# TU_ADV_SCH.net
KiCad netlist of a schematic drawn in Altium Designer
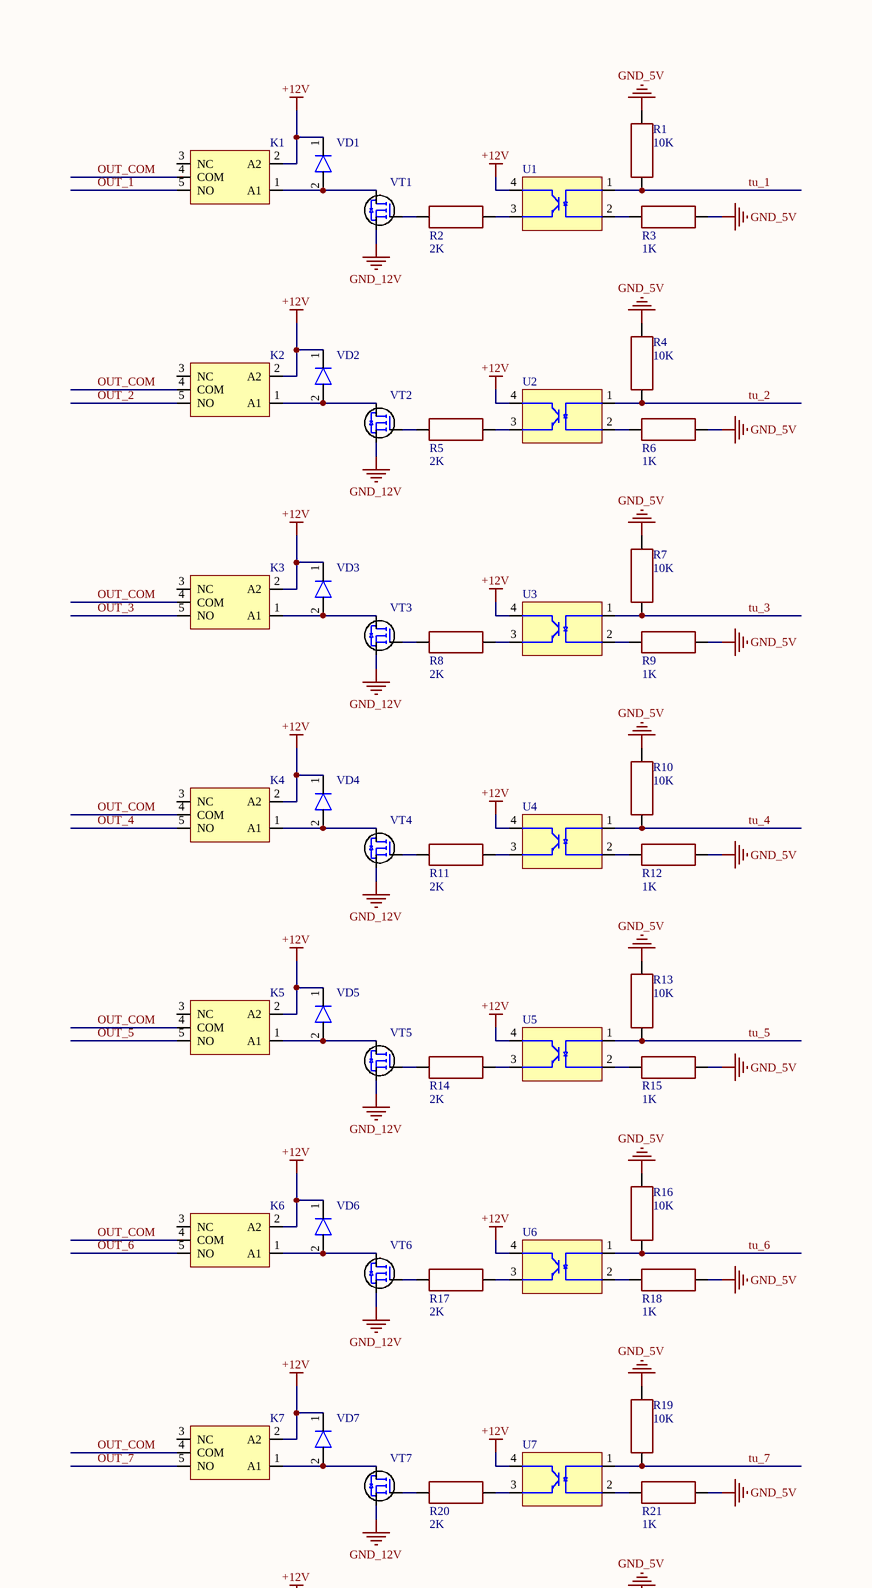
[diagram p0: TU_ADV_SCH.SchDoc, row 1 of 5 left]
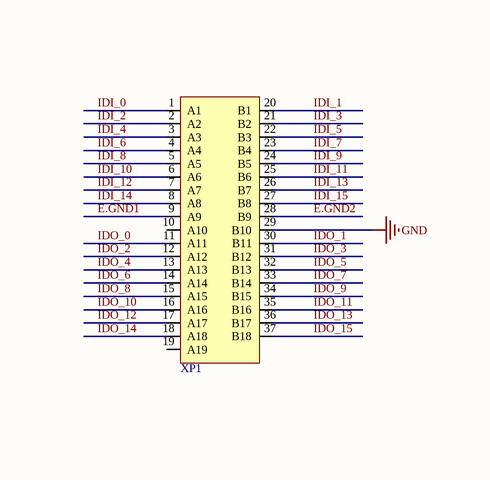
[diagram p1: TU_ADV_SCH.SchDoc, row 1 of 5 right]
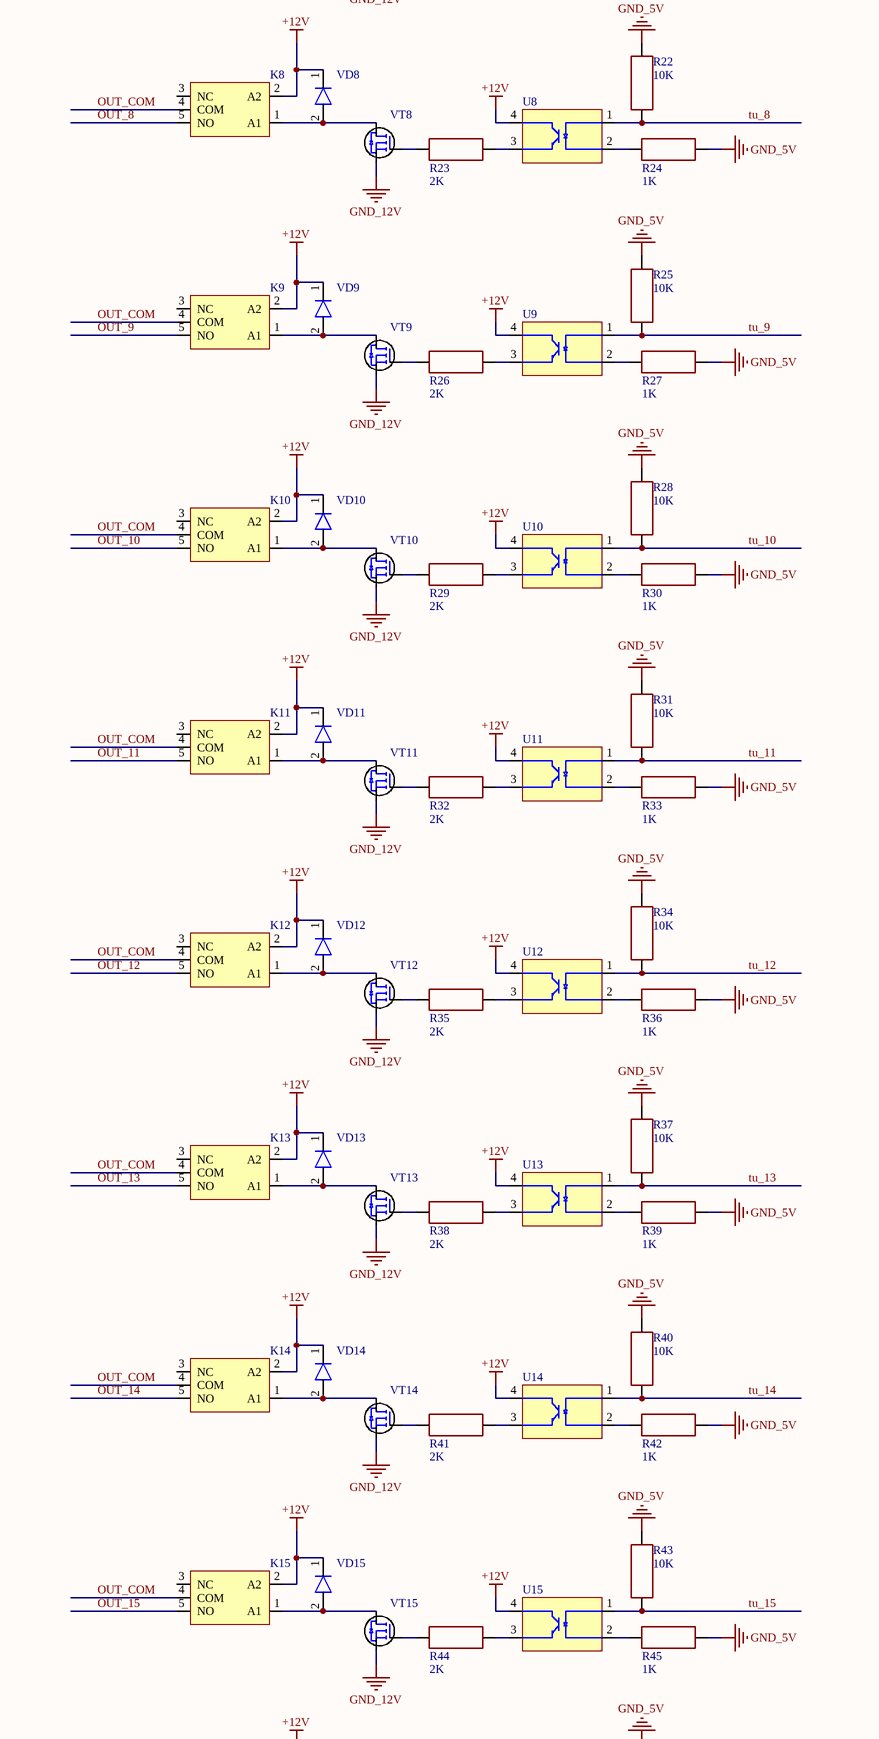
[diagram p2: TU_ADV_SCH.SchDoc, row 2 of 5 left]
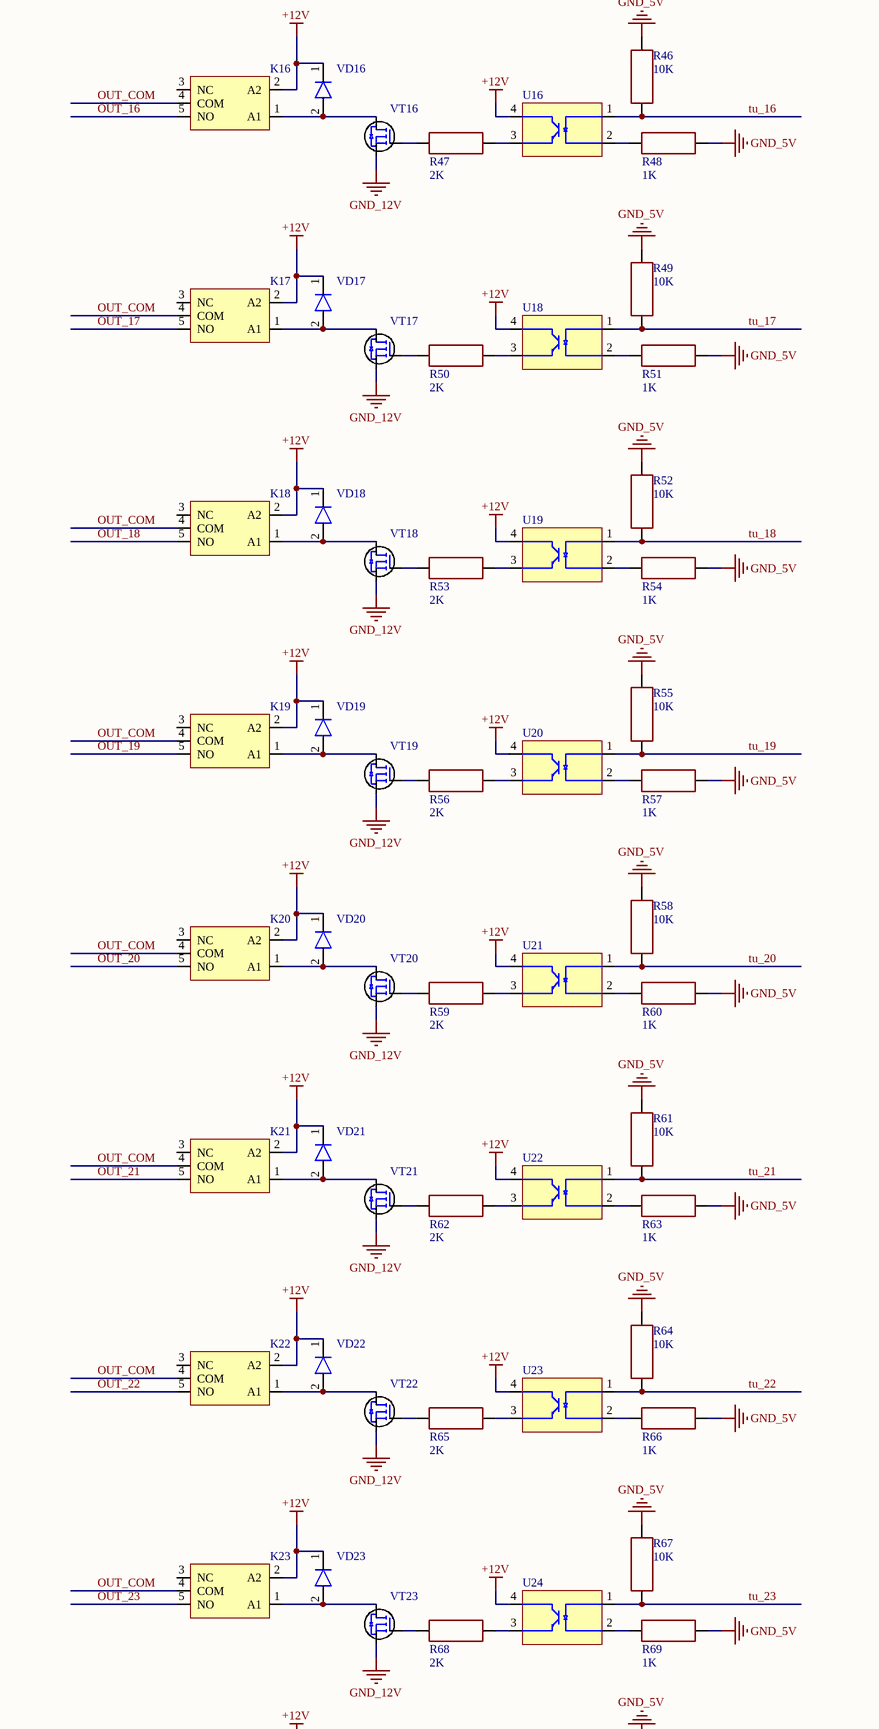
[diagram p3: TU_ADV_SCH.SchDoc, row 3 of 5 left]
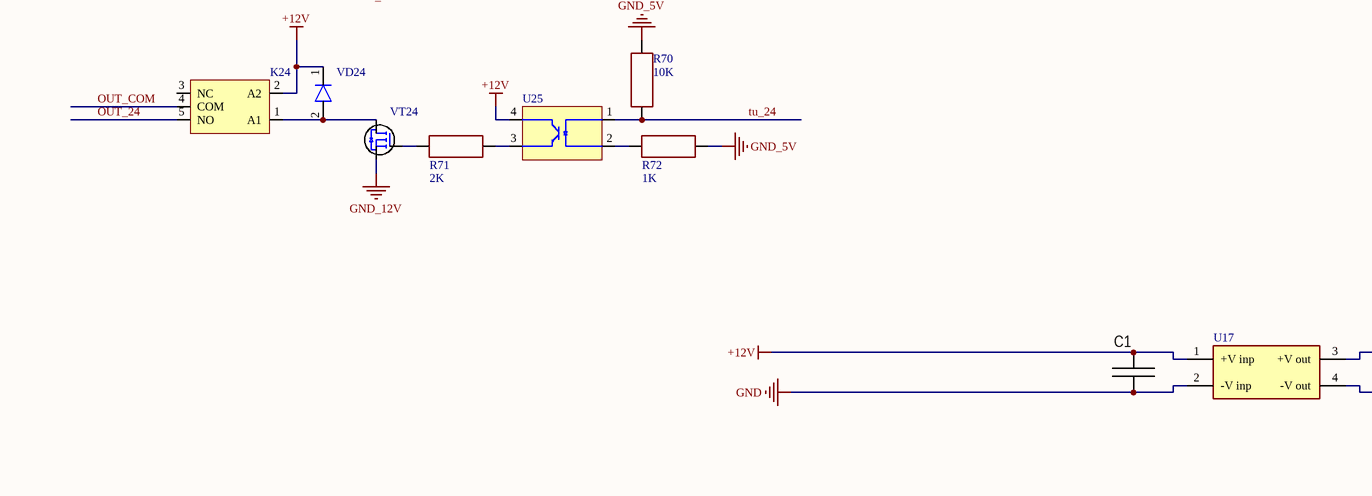
[diagram p4: TU_ADV_SCH.SchDoc, row 4 of 5 left]
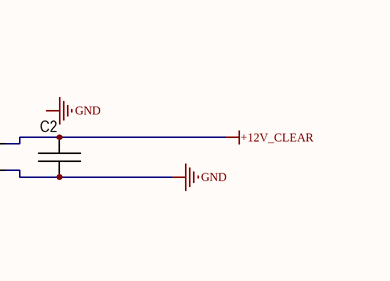
[diagram p5: TU_ADV_SCH.SchDoc, row 4 of 5 right]
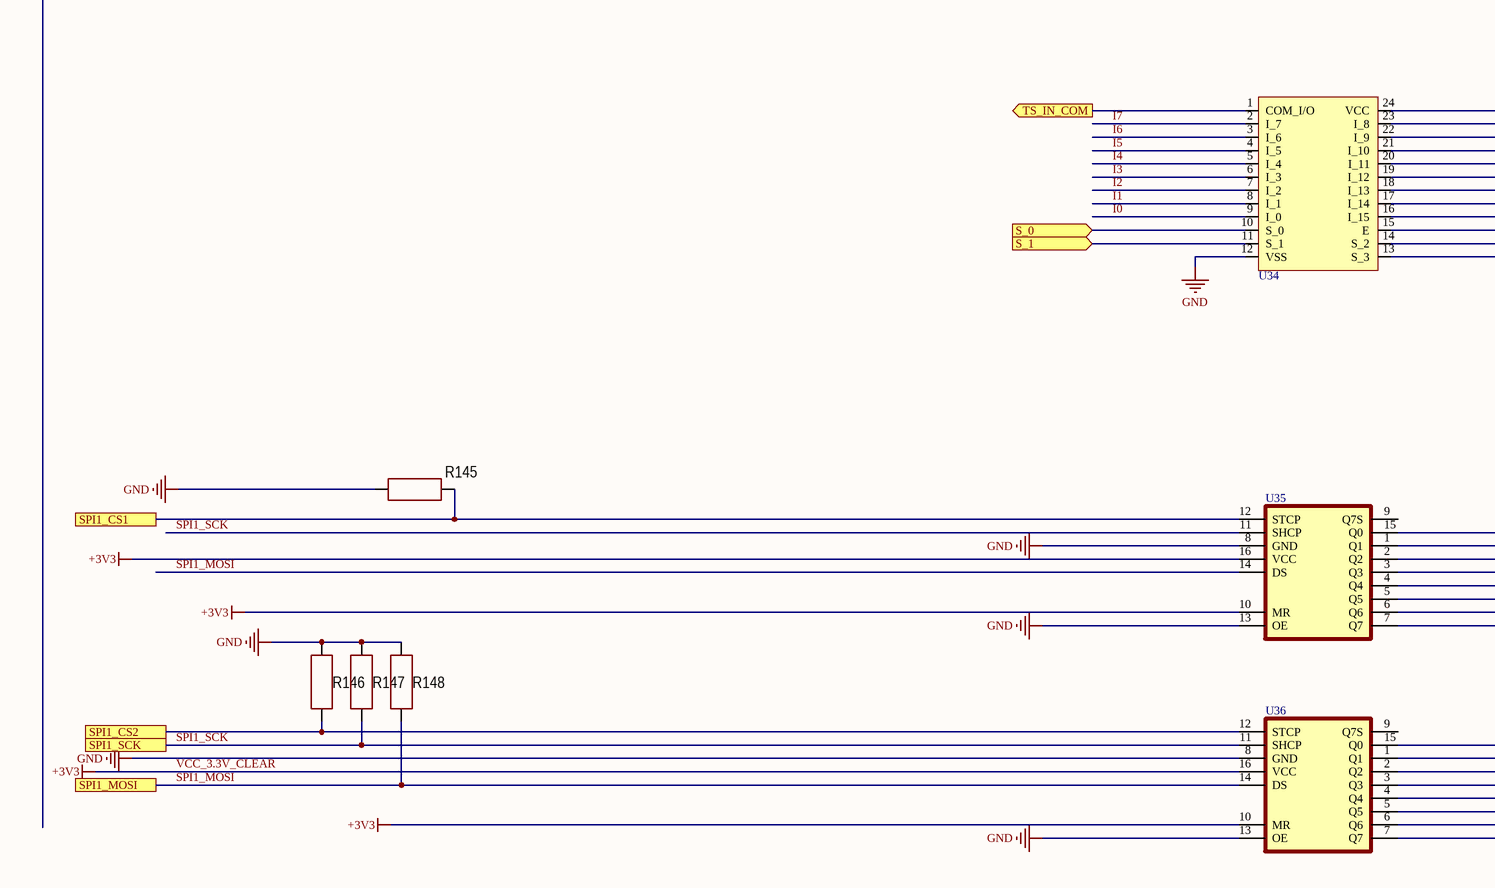
[diagram p6: TU_ADV_SCH.SchDoc, row 5 of 5 left]
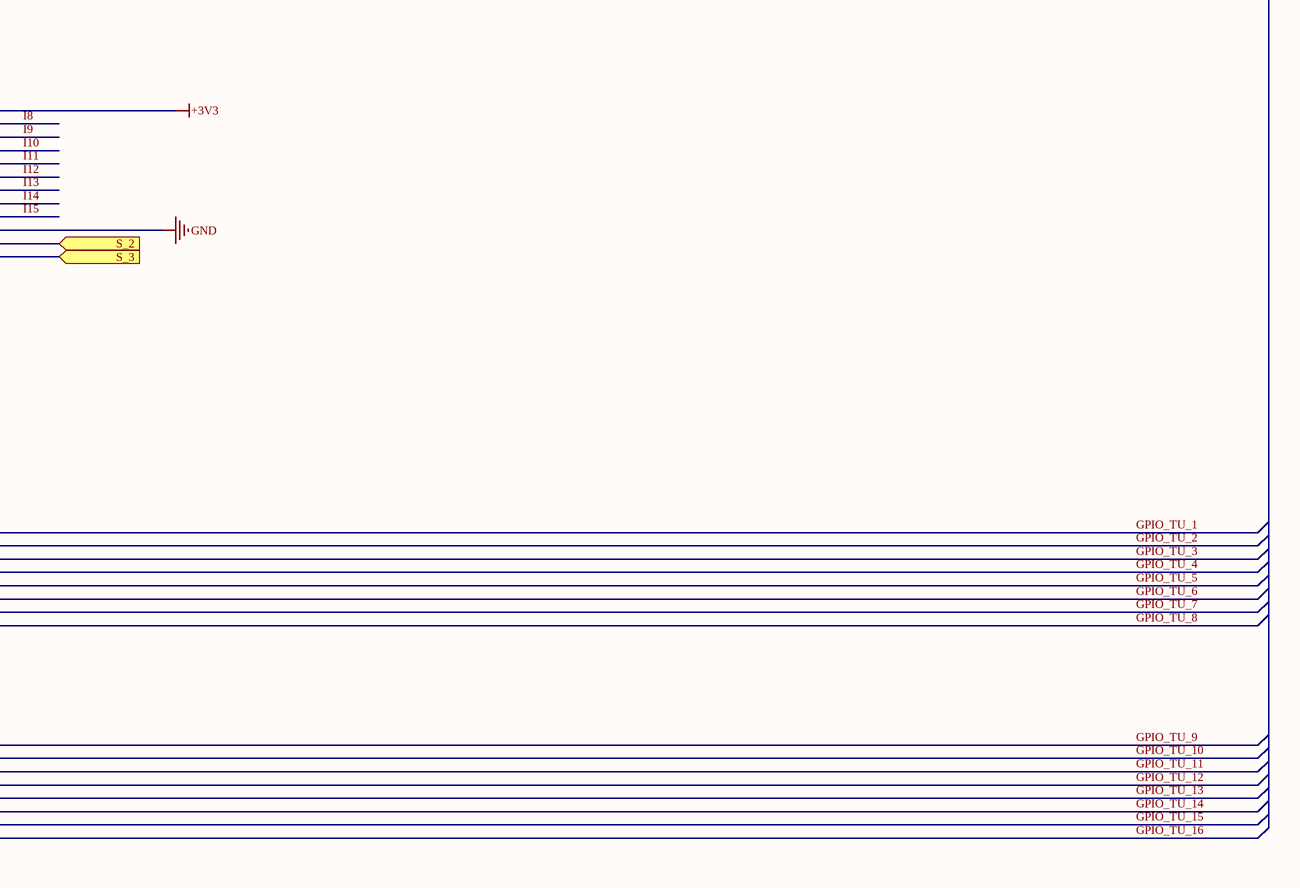
[diagram p7: TU_ADV_SCH.SchDoc, row 5 of 5 right]

(export (version "E")
  (design (tool "Eeschema 10.0.6"))
  (components
    (comp (ref "C1") (value "~") (footprint "CAP: 2220") (libsource (lib "capacitor") (part "Ceramic_2220")))
    (comp (ref "C2") (value "~") (footprint "CAP: 2220") (libsource (lib "capacitor") (part "Ceramic_2220")))
    (comp (ref "K1")
      (value "RM96-3011-35-1012")
      (footprint "RM96")
      (description "Relay 12V DC; 8А; 8A/250ВAC;")
      (fields (field (name "MANUFACTURER") "Производитель"))
      (libsource (lib "MY_INT_LIB") (part "RM96-3011-35-1012"))
    )
    (comp (ref "K2")
      (value "RM96-3011-35-1012")
      (footprint "RM96")
      (description "Relay 12V DC; 8А; 8A/250ВAC;")
      (fields (field (name "MANUFACTURER") "Производитель"))
      (libsource (lib "MY_INT_LIB") (part "RM96-3011-35-1012"))
    )
    (comp (ref "K3")
      (value "RM96-3011-35-1012")
      (footprint "RM96")
      (description "Relay 12V DC; 8А; 8A/250ВAC;")
      (fields (field (name "MANUFACTURER") "Производитель"))
      (libsource (lib "MY_INT_LIB") (part "RM96-3011-35-1012"))
    )
    (comp (ref "K4")
      (value "RM96-3011-35-1012")
      (footprint "RM96")
      (description "Relay 12V DC; 8А; 8A/250ВAC;")
      (fields (field (name "MANUFACTURER") "Производитель"))
      (libsource (lib "MY_INT_LIB") (part "RM96-3011-35-1012"))
    )
    (comp (ref "K5")
      (value "RM96-3011-35-1012")
      (footprint "RM96")
      (description "Relay 12V DC; 8А; 8A/250ВAC;")
      (fields (field (name "MANUFACTURER") "Производитель"))
      (libsource (lib "MY_INT_LIB") (part "RM96-3011-35-1012"))
    )
    (comp (ref "K6")
      (value "RM96-3011-35-1012")
      (footprint "RM96")
      (description "Relay 12V DC; 8А; 8A/250ВAC;")
      (fields (field (name "MANUFACTURER") "Производитель"))
      (libsource (lib "MY_INT_LIB") (part "RM96-3011-35-1012"))
    )
    (comp (ref "K7")
      (value "RM96-3011-35-1012")
      (footprint "RM96")
      (description "Relay 12V DC; 8А; 8A/250ВAC;")
      (fields (field (name "MANUFACTURER") "Производитель"))
      (libsource (lib "MY_INT_LIB") (part "RM96-3011-35-1012"))
    )
    (comp (ref "K8")
      (value "RM96-3011-35-1012")
      (footprint "RM96")
      (description "Relay 12V DC; 8А; 8A/250ВAC;")
      (fields (field (name "MANUFACTURER") "Производитель"))
      (libsource (lib "MY_INT_LIB") (part "RM96-3011-35-1012"))
    )
    (comp (ref "K9")
      (value "RM96-3011-35-1012")
      (footprint "RM96")
      (description "Relay 12V DC; 8А; 8A/250ВAC;")
      (fields (field (name "MANUFACTURER") "Производитель"))
      (libsource (lib "MY_INT_LIB") (part "RM96-3011-35-1012"))
    )
    (comp (ref "K10")
      (value "RM96-3011-35-1012")
      (footprint "RM96")
      (description "Relay 12V DC; 8А; 8A/250ВAC;")
      (fields (field (name "MANUFACTURER") "Производитель"))
      (libsource (lib "MY_INT_LIB") (part "RM96-3011-35-1012"))
    )
    (comp (ref "K11")
      (value "RM96-3011-35-1012")
      (footprint "RM96")
      (description "Relay 12V DC; 8А; 8A/250ВAC;")
      (fields (field (name "MANUFACTURER") "Производитель"))
      (libsource (lib "MY_INT_LIB") (part "RM96-3011-35-1012"))
    )
    (comp (ref "K12")
      (value "RM96-3011-35-1012")
      (footprint "RM96")
      (description "Relay 12V DC; 8А; 8A/250ВAC;")
      (fields (field (name "MANUFACTURER") "Производитель"))
      (libsource (lib "MY_INT_LIB") (part "RM96-3011-35-1012"))
    )
    (comp (ref "K13")
      (value "RM96-3011-35-1012")
      (footprint "RM96")
      (description "Relay 12V DC; 8А; 8A/250ВAC;")
      (fields (field (name "MANUFACTURER") "Производитель"))
      (libsource (lib "MY_INT_LIB") (part "RM96-3011-35-1012"))
    )
    (comp (ref "K14")
      (value "RM96-3011-35-1012")
      (footprint "RM96")
      (description "Relay 12V DC; 8А; 8A/250ВAC;")
      (fields (field (name "MANUFACTURER") "Производитель"))
      (libsource (lib "MY_INT_LIB") (part "RM96-3011-35-1012"))
    )
    (comp (ref "K15")
      (value "RM96-3011-35-1012")
      (footprint "RM96")
      (description "Relay 12V DC; 8А; 8A/250ВAC;")
      (fields (field (name "MANUFACTURER") "Производитель"))
      (libsource (lib "MY_INT_LIB") (part "RM96-3011-35-1012"))
    )
    (comp (ref "K16")
      (value "RM96-3011-35-1012")
      (footprint "RM96")
      (description "Relay 12V DC; 8А; 8A/250ВAC;")
      (fields (field (name "MANUFACTURER") "Производитель"))
      (libsource (lib "MY_INT_LIB") (part "RM96-3011-35-1012"))
    )
    (comp (ref "K17")
      (value "RM96-3011-35-1012")
      (footprint "RM96")
      (description "Relay 12V DC; 8А; 8A/250ВAC;")
      (fields (field (name "MANUFACTURER") "Производитель"))
      (libsource (lib "MY_INT_LIB") (part "RM96-3011-35-1012"))
    )
    (comp (ref "K18")
      (value "RM96-3011-35-1012")
      (footprint "RM96")
      (description "Relay 12V DC; 8А; 8A/250ВAC;")
      (fields (field (name "MANUFACTURER") "Производитель"))
      (libsource (lib "MY_INT_LIB") (part "RM96-3011-35-1012"))
    )
    (comp (ref "K19")
      (value "RM96-3011-35-1012")
      (footprint "RM96")
      (description "Relay 12V DC; 8А; 8A/250ВAC;")
      (fields (field (name "MANUFACTURER") "Производитель"))
      (libsource (lib "MY_INT_LIB") (part "RM96-3011-35-1012"))
    )
    (comp (ref "K20")
      (value "RM96-3011-35-1012")
      (footprint "RM96")
      (description "Relay 12V DC; 8А; 8A/250ВAC;")
      (fields (field (name "MANUFACTURER") "Производитель"))
      (libsource (lib "MY_INT_LIB") (part "RM96-3011-35-1012"))
    )
    (comp (ref "K21")
      (value "RM96-3011-35-1012")
      (footprint "RM96")
      (description "Relay 12V DC; 8А; 8A/250ВAC;")
      (fields (field (name "MANUFACTURER") "Производитель"))
      (libsource (lib "MY_INT_LIB") (part "RM96-3011-35-1012"))
    )
    (comp (ref "K22")
      (value "RM96-3011-35-1012")
      (footprint "RM96")
      (description "Relay 12V DC; 8А; 8A/250ВAC;")
      (fields (field (name "MANUFACTURER") "Производитель"))
      (libsource (lib "MY_INT_LIB") (part "RM96-3011-35-1012"))
    )
    (comp (ref "K23")
      (value "RM96-3011-35-1012")
      (footprint "RM96")
      (description "Relay 12V DC; 8А; 8A/250ВAC;")
      (fields (field (name "MANUFACTURER") "Производитель"))
      (libsource (lib "MY_INT_LIB") (part "RM96-3011-35-1012"))
    )
    (comp (ref "K24")
      (value "RM96-3011-35-1012")
      (footprint "RM96")
      (description "Relay 12V DC; 8А; 8A/250ВAC;")
      (fields (field (name "MANUFACTURER") "Производитель"))
      (libsource (lib "MY_INT_LIB") (part "RM96-3011-35-1012"))
    )
    (comp (ref "R1")
      (value "10K")
      (footprint "RES: 0402")
      (fields (field (name "TOLERANCE") "±5%"))
      (libsource (lib "") (part "Resistor_0402_2"))
    )
    (comp (ref "R2")
      (value "2K")
      (footprint "RES: 0402")
      (fields (field (name "TOLERANCE") "±5%"))
      (libsource (lib "") (part "Resistor_0402_1"))
    )
    (comp (ref "R3")
      (value "1K")
      (footprint "RES: 0402")
      (fields (field (name "TOLERANCE") "±5%"))
      (libsource (lib "resistor") (part "Resistor_0402"))
    )
    (comp (ref "R4")
      (value "10K")
      (footprint "RES: 0402")
      (fields (field (name "TOLERANCE") "±5%"))
      (libsource (lib "") (part "Resistor_0402_2"))
    )
    (comp (ref "R5")
      (value "2K")
      (footprint "RES: 0402")
      (fields (field (name "TOLERANCE") "±5%"))
      (libsource (lib "") (part "Resistor_0402_1"))
    )
    (comp (ref "R6")
      (value "1K")
      (footprint "RES: 0402")
      (fields (field (name "TOLERANCE") "±5%"))
      (libsource (lib "resistor") (part "Resistor_0402"))
    )
    (comp (ref "R7")
      (value "10K")
      (footprint "RES: 0402")
      (fields (field (name "TOLERANCE") "±5%"))
      (libsource (lib "") (part "Resistor_0402_2"))
    )
    (comp (ref "R8")
      (value "2K")
      (footprint "RES: 0402")
      (fields (field (name "TOLERANCE") "±5%"))
      (libsource (lib "") (part "Resistor_0402_1"))
    )
    (comp (ref "R9")
      (value "1K")
      (footprint "RES: 0402")
      (fields (field (name "TOLERANCE") "±5%"))
      (libsource (lib "resistor") (part "Resistor_0402"))
    )
    (comp (ref "R10")
      (value "10K")
      (footprint "RES: 0402")
      (fields (field (name "TOLERANCE") "±5%"))
      (libsource (lib "") (part "Resistor_0402_2"))
    )
    (comp (ref "R11")
      (value "2K")
      (footprint "RES: 0402")
      (fields (field (name "TOLERANCE") "±5%"))
      (libsource (lib "") (part "Resistor_0402_1"))
    )
    (comp (ref "R12")
      (value "1K")
      (footprint "RES: 0402")
      (fields (field (name "TOLERANCE") "±5%"))
      (libsource (lib "resistor") (part "Resistor_0402"))
    )
    (comp (ref "R13")
      (value "10K")
      (footprint "RES: 0402")
      (fields (field (name "TOLERANCE") "±5%"))
      (libsource (lib "") (part "Resistor_0402_2"))
    )
    (comp (ref "R14")
      (value "2K")
      (footprint "RES: 0402")
      (fields (field (name "TOLERANCE") "±5%"))
      (libsource (lib "") (part "Resistor_0402_1"))
    )
    (comp (ref "R15")
      (value "1K")
      (footprint "RES: 0402")
      (fields (field (name "TOLERANCE") "±5%"))
      (libsource (lib "resistor") (part "Resistor_0402"))
    )
    (comp (ref "R16")
      (value "10K")
      (footprint "RES: 0402")
      (fields (field (name "TOLERANCE") "±5%"))
      (libsource (lib "") (part "Resistor_0402_2"))
    )
    (comp (ref "R17")
      (value "2K")
      (footprint "RES: 0402")
      (fields (field (name "TOLERANCE") "±5%"))
      (libsource (lib "") (part "Resistor_0402_1"))
    )
    (comp (ref "R18")
      (value "1K")
      (footprint "RES: 0402")
      (fields (field (name "TOLERANCE") "±5%"))
      (libsource (lib "resistor") (part "Resistor_0402"))
    )
    (comp (ref "R19")
      (value "10K")
      (footprint "RES: 0402")
      (fields (field (name "TOLERANCE") "±5%"))
      (libsource (lib "") (part "Resistor_0402_2"))
    )
    (comp (ref "R20")
      (value "2K")
      (footprint "RES: 0402")
      (fields (field (name "TOLERANCE") "±5%"))
      (libsource (lib "") (part "Resistor_0402_1"))
    )
    (comp (ref "R21")
      (value "1K")
      (footprint "RES: 0402")
      (fields (field (name "TOLERANCE") "±5%"))
      (libsource (lib "resistor") (part "Resistor_0402"))
    )
    (comp (ref "R22")
      (value "10K")
      (footprint "RES: 0402")
      (fields (field (name "TOLERANCE") "±5%"))
      (libsource (lib "") (part "Resistor_0402_2"))
    )
    (comp (ref "R23")
      (value "2K")
      (footprint "RES: 0402")
      (fields (field (name "TOLERANCE") "±5%"))
      (libsource (lib "") (part "Resistor_0402_1"))
    )
    (comp (ref "R24")
      (value "1K")
      (footprint "RES: 0402")
      (fields (field (name "TOLERANCE") "±5%"))
      (libsource (lib "resistor") (part "Resistor_0402"))
    )
    (comp (ref "R25")
      (value "10K")
      (footprint "RES: 0402")
      (fields (field (name "TOLERANCE") "±5%"))
      (libsource (lib "") (part "Resistor_0402_2"))
    )
    (comp (ref "R26")
      (value "2K")
      (footprint "RES: 0402")
      (fields (field (name "TOLERANCE") "±5%"))
      (libsource (lib "") (part "Resistor_0402_1"))
    )
    (comp (ref "R27")
      (value "1K")
      (footprint "RES: 0402")
      (fields (field (name "TOLERANCE") "±5%"))
      (libsource (lib "resistor") (part "Resistor_0402"))
    )
    (comp (ref "R28")
      (value "10K")
      (footprint "RES: 0402")
      (fields (field (name "TOLERANCE") "±5%"))
      (libsource (lib "") (part "Resistor_0402_2"))
    )
    (comp (ref "R29")
      (value "2K")
      (footprint "RES: 0402")
      (fields (field (name "TOLERANCE") "±5%"))
      (libsource (lib "") (part "Resistor_0402_1"))
    )
    (comp (ref "R30")
      (value "1K")
      (footprint "RES: 0402")
      (fields (field (name "TOLERANCE") "±5%"))
      (libsource (lib "resistor") (part "Resistor_0402"))
    )
    (comp (ref "R31")
      (value "10K")
      (footprint "RES: 0402")
      (fields (field (name "TOLERANCE") "±5%"))
      (libsource (lib "") (part "Resistor_0402_2"))
    )
    (comp (ref "R32")
      (value "2K")
      (footprint "RES: 0402")
      (fields (field (name "TOLERANCE") "±5%"))
      (libsource (lib "") (part "Resistor_0402_1"))
    )
    (comp (ref "R33")
      (value "1K")
      (footprint "RES: 0402")
      (fields (field (name "TOLERANCE") "±5%"))
      (libsource (lib "resistor") (part "Resistor_0402"))
    )
    (comp (ref "R34")
      (value "10K")
      (footprint "RES: 0402")
      (fields (field (name "TOLERANCE") "±5%"))
      (libsource (lib "") (part "Resistor_0402_2"))
    )
    (comp (ref "R35")
      (value "2K")
      (footprint "RES: 0402")
      (fields (field (name "TOLERANCE") "±5%"))
      (libsource (lib "") (part "Resistor_0402_1"))
    )
    (comp (ref "R36")
      (value "1K")
      (footprint "RES: 0402")
      (fields (field (name "TOLERANCE") "±5%"))
      (libsource (lib "resistor") (part "Resistor_0402"))
    )
    (comp (ref "R37")
      (value "10K")
      (footprint "RES: 0402")
      (fields (field (name "TOLERANCE") "±5%"))
      (libsource (lib "") (part "Resistor_0402_2"))
    )
    (comp (ref "R38")
      (value "2K")
      (footprint "RES: 0402")
      (fields (field (name "TOLERANCE") "±5%"))
      (libsource (lib "") (part "Resistor_0402_1"))
    )
    (comp (ref "R39")
      (value "1K")
      (footprint "RES: 0402")
      (fields (field (name "TOLERANCE") "±5%"))
      (libsource (lib "resistor") (part "Resistor_0402"))
    )
    (comp (ref "R40")
      (value "10K")
      (footprint "RES: 0402")
      (fields (field (name "TOLERANCE") "±5%"))
      (libsource (lib "") (part "Resistor_0402_2"))
    )
    (comp (ref "R41")
      (value "2K")
      (footprint "RES: 0402")
      (fields (field (name "TOLERANCE") "±5%"))
      (libsource (lib "") (part "Resistor_0402_1"))
    )
    (comp (ref "R42")
      (value "1K")
      (footprint "RES: 0402")
      (fields (field (name "TOLERANCE") "±5%"))
      (libsource (lib "resistor") (part "Resistor_0402"))
    )
    (comp (ref "R43")
      (value "10K")
      (footprint "RES: 0402")
      (fields (field (name "TOLERANCE") "±5%"))
      (libsource (lib "") (part "Resistor_0402_2"))
    )
    (comp (ref "R44")
      (value "2K")
      (footprint "RES: 0402")
      (fields (field (name "TOLERANCE") "±5%"))
      (libsource (lib "") (part "Resistor_0402_1"))
    )
    (comp (ref "R45")
      (value "1K")
      (footprint "RES: 0402")
      (fields (field (name "TOLERANCE") "±5%"))
      (libsource (lib "resistor") (part "Resistor_0402"))
    )
    (comp (ref "R46")
      (value "10K")
      (footprint "RES: 0402")
      (fields (field (name "TOLERANCE") "±5%"))
      (libsource (lib "") (part "Resistor_0402_2"))
    )
    (comp (ref "R47")
      (value "2K")
      (footprint "RES: 0402")
      (fields (field (name "TOLERANCE") "±5%"))
      (libsource (lib "") (part "Resistor_0402_1"))
    )
    (comp (ref "R48")
      (value "1K")
      (footprint "RES: 0402")
      (fields (field (name "TOLERANCE") "±5%"))
      (libsource (lib "resistor") (part "Resistor_0402"))
    )
    (comp (ref "R49")
      (value "10K")
      (footprint "RES: 0402")
      (fields (field (name "TOLERANCE") "±5%"))
      (libsource (lib "") (part "Resistor_0402_2"))
    )
    (comp (ref "R50")
      (value "2K")
      (footprint "RES: 0402")
      (fields (field (name "TOLERANCE") "±5%"))
      (libsource (lib "") (part "Resistor_0402_1"))
    )
    (comp (ref "R51")
      (value "1K")
      (footprint "RES: 0402")
      (fields (field (name "TOLERANCE") "±5%"))
      (libsource (lib "resistor") (part "Resistor_0402"))
    )
    (comp (ref "R52")
      (value "10K")
      (footprint "RES: 0402")
      (fields (field (name "TOLERANCE") "±5%"))
      (libsource (lib "") (part "Resistor_0402_2"))
    )
    (comp (ref "R53")
      (value "2K")
      (footprint "RES: 0402")
      (fields (field (name "TOLERANCE") "±5%"))
      (libsource (lib "") (part "Resistor_0402_1"))
    )
    (comp (ref "R54")
      (value "1K")
      (footprint "RES: 0402")
      (fields (field (name "TOLERANCE") "±5%"))
      (libsource (lib "resistor") (part "Resistor_0402"))
    )
    (comp (ref "R55")
      (value "10K")
      (footprint "RES: 0402")
      (fields (field (name "TOLERANCE") "±5%"))
      (libsource (lib "") (part "Resistor_0402_2"))
    )
    (comp (ref "R56")
      (value "2K")
      (footprint "RES: 0402")
      (fields (field (name "TOLERANCE") "±5%"))
      (libsource (lib "") (part "Resistor_0402_1"))
    )
    (comp (ref "R57")
      (value "1K")
      (footprint "RES: 0402")
      (fields (field (name "TOLERANCE") "±5%"))
      (libsource (lib "resistor") (part "Resistor_0402"))
    )
    (comp (ref "R58")
      (value "10K")
      (footprint "RES: 0402")
      (fields (field (name "TOLERANCE") "±5%"))
      (libsource (lib "") (part "Resistor_0402_2"))
    )
    (comp (ref "R59")
      (value "2K")
      (footprint "RES: 0402")
      (fields (field (name "TOLERANCE") "±5%"))
      (libsource (lib "") (part "Resistor_0402_1"))
    )
    (comp (ref "R60")
      (value "1K")
      (footprint "RES: 0402")
      (fields (field (name "TOLERANCE") "±5%"))
      (libsource (lib "resistor") (part "Resistor_0402"))
    )
    (comp (ref "R61")
      (value "10K")
      (footprint "RES: 0402")
      (fields (field (name "TOLERANCE") "±5%"))
      (libsource (lib "") (part "Resistor_0402_2"))
    )
    (comp (ref "R62")
      (value "2K")
      (footprint "RES: 0402")
      (fields (field (name "TOLERANCE") "±5%"))
      (libsource (lib "") (part "Resistor_0402_1"))
    )
    (comp (ref "R63")
      (value "1K")
      (footprint "RES: 0402")
      (fields (field (name "TOLERANCE") "±5%"))
      (libsource (lib "resistor") (part "Resistor_0402"))
    )
    (comp (ref "R64")
      (value "10K")
      (footprint "RES: 0402")
      (fields (field (name "TOLERANCE") "±5%"))
      (libsource (lib "") (part "Resistor_0402_2"))
    )
    (comp (ref "R65")
      (value "2K")
      (footprint "RES: 0402")
      (fields (field (name "TOLERANCE") "±5%"))
      (libsource (lib "") (part "Resistor_0402_1"))
    )
    (comp (ref "R66")
      (value "1K")
      (footprint "RES: 0402")
      (fields (field (name "TOLERANCE") "±5%"))
      (libsource (lib "resistor") (part "Resistor_0402"))
    )
    (comp (ref "R67")
      (value "10K")
      (footprint "RES: 0402")
      (fields (field (name "TOLERANCE") "±5%"))
      (libsource (lib "") (part "Resistor_0402_2"))
    )
    (comp (ref "R68")
      (value "2K")
      (footprint "RES: 0402")
      (fields (field (name "TOLERANCE") "±5%"))
      (libsource (lib "") (part "Resistor_0402_1"))
    )
    (comp (ref "R69")
      (value "1K")
      (footprint "RES: 0402")
      (fields (field (name "TOLERANCE") "±5%"))
      (libsource (lib "resistor") (part "Resistor_0402"))
    )
    (comp (ref "R70")
      (value "10K")
      (footprint "RES: 0402")
      (fields (field (name "TOLERANCE") "±5%"))
      (libsource (lib "") (part "Resistor_0402_2"))
    )
    (comp (ref "R71")
      (value "2K")
      (footprint "RES: 0402")
      (fields (field (name "TOLERANCE") "±5%"))
      (libsource (lib "") (part "Resistor_0402_1"))
    )
    (comp (ref "R72")
      (value "1K")
      (footprint "RES: 0402")
      (fields (field (name "TOLERANCE") "±5%"))
      (libsource (lib "resistor") (part "Resistor_0402"))
    )
    (comp (ref "R145") (value "~") (footprint "RES: 0603") (libsource (lib "") (part "Resistor_0603_1")))
    (comp (ref "R146")
      (value "~")
      (footprint "RES: 0603")
      (libsource (lib "resistor") (part "Resistor_0603"))
    )
    (comp (ref "R147")
      (value "~")
      (footprint "RES: 0603")
      (libsource (lib "resistor") (part "Resistor_0603"))
    )
    (comp (ref "R148")
      (value "~")
      (footprint "RES: 0603")
      (libsource (lib "resistor") (part "Resistor_0603"))
    )
    (comp (ref "U1")
      (value "LTV-357T")
      (footprint "SMD-4")
      (description "Transistor Output Optocouplers Optocoupler Phototrans")
      (fields (field (name "MANUFACTURER") "Lite-On"))
      (libsource (lib "MY_INT_LIB") (part "LTV-357T"))
    )
    (comp (ref "U2")
      (value "LTV-357T")
      (footprint "SMD-4")
      (description "Transistor Output Optocouplers Optocoupler Phototrans")
      (fields (field (name "MANUFACTURER") "Lite-On"))
      (libsource (lib "MY_INT_LIB") (part "LTV-357T"))
    )
    (comp (ref "U3")
      (value "LTV-357T")
      (footprint "SMD-4")
      (description "Transistor Output Optocouplers Optocoupler Phototrans")
      (fields (field (name "MANUFACTURER") "Lite-On"))
      (libsource (lib "MY_INT_LIB") (part "LTV-357T"))
    )
    (comp (ref "U4")
      (value "LTV-357T")
      (footprint "SMD-4")
      (description "Transistor Output Optocouplers Optocoupler Phototrans")
      (fields (field (name "MANUFACTURER") "Lite-On"))
      (libsource (lib "MY_INT_LIB") (part "LTV-357T"))
    )
    (comp (ref "U5")
      (value "LTV-357T")
      (footprint "SMD-4")
      (description "Transistor Output Optocouplers Optocoupler Phototrans")
      (fields (field (name "MANUFACTURER") "Lite-On"))
      (libsource (lib "MY_INT_LIB") (part "LTV-357T"))
    )
    (comp (ref "U6")
      (value "LTV-357T")
      (footprint "SMD-4")
      (description "Transistor Output Optocouplers Optocoupler Phototrans")
      (fields (field (name "MANUFACTURER") "Lite-On"))
      (libsource (lib "MY_INT_LIB") (part "LTV-357T"))
    )
    (comp (ref "U7")
      (value "LTV-357T")
      (footprint "SMD-4")
      (description "Transistor Output Optocouplers Optocoupler Phototrans")
      (fields (field (name "MANUFACTURER") "Lite-On"))
      (libsource (lib "MY_INT_LIB") (part "LTV-357T"))
    )
    (comp (ref "U8")
      (value "LTV-357T")
      (footprint "SMD-4")
      (description "Transistor Output Optocouplers Optocoupler Phototrans")
      (fields (field (name "MANUFACTURER") "Lite-On"))
      (libsource (lib "MY_INT_LIB") (part "LTV-357T"))
    )
    (comp (ref "U9")
      (value "LTV-357T")
      (footprint "SMD-4")
      (description "Transistor Output Optocouplers Optocoupler Phototrans")
      (fields (field (name "MANUFACTURER") "Lite-On"))
      (libsource (lib "MY_INT_LIB") (part "LTV-357T"))
    )
    (comp (ref "U10")
      (value "LTV-357T")
      (footprint "SMD-4")
      (description "Transistor Output Optocouplers Optocoupler Phototrans")
      (fields (field (name "MANUFACTURER") "Lite-On"))
      (libsource (lib "MY_INT_LIB") (part "LTV-357T"))
    )
    (comp (ref "U11")
      (value "LTV-357T")
      (footprint "SMD-4")
      (description "Transistor Output Optocouplers Optocoupler Phototrans")
      (fields (field (name "MANUFACTURER") "Lite-On"))
      (libsource (lib "MY_INT_LIB") (part "LTV-357T"))
    )
    (comp (ref "U12")
      (value "LTV-357T")
      (footprint "SMD-4")
      (description "Transistor Output Optocouplers Optocoupler Phototrans")
      (fields (field (name "MANUFACTURER") "Lite-On"))
      (libsource (lib "MY_INT_LIB") (part "LTV-357T"))
    )
    (comp (ref "U13")
      (value "LTV-357T")
      (footprint "SMD-4")
      (description "Transistor Output Optocouplers Optocoupler Phototrans")
      (fields (field (name "MANUFACTURER") "Lite-On"))
      (libsource (lib "MY_INT_LIB") (part "LTV-357T"))
    )
    (comp (ref "U14")
      (value "LTV-357T")
      (footprint "SMD-4")
      (description "Transistor Output Optocouplers Optocoupler Phototrans")
      (fields (field (name "MANUFACTURER") "Lite-On"))
      (libsource (lib "MY_INT_LIB") (part "LTV-357T"))
    )
    (comp (ref "U15")
      (value "LTV-357T")
      (footprint "SMD-4")
      (description "Transistor Output Optocouplers Optocoupler Phototrans")
      (fields (field (name "MANUFACTURER") "Lite-On"))
      (libsource (lib "MY_INT_LIB") (part "LTV-357T"))
    )
    (comp (ref "U16")
      (value "LTV-357T")
      (footprint "SMD-4")
      (description "Transistor Output Optocouplers Optocoupler Phototrans")
      (fields (field (name "MANUFACTURER") "Lite-On"))
      (libsource (lib "MY_INT_LIB") (part "LTV-357T"))
    )
    (comp (ref "U17")
      (value "AM1D-1212SH")
      (footprint "AM1D-1212SH")
      (description "Linear Voltage Regulator IC 1 Output 800mA SOT-223")
      (libsource (lib "AM1D-1212SH") (part "AM1D-1212SH"))
    )
    (comp (ref "U18")
      (value "LTV-357T")
      (footprint "SMD-4")
      (description "Transistor Output Optocouplers Optocoupler Phototrans")
      (fields (field (name "MANUFACTURER") "Lite-On"))
      (libsource (lib "MY_INT_LIB") (part "LTV-357T"))
    )
    (comp (ref "U19")
      (value "LTV-357T")
      (footprint "SMD-4")
      (description "Transistor Output Optocouplers Optocoupler Phototrans")
      (fields (field (name "MANUFACTURER") "Lite-On"))
      (libsource (lib "MY_INT_LIB") (part "LTV-357T"))
    )
    (comp (ref "U20")
      (value "LTV-357T")
      (footprint "SMD-4")
      (description "Transistor Output Optocouplers Optocoupler Phototrans")
      (fields (field (name "MANUFACTURER") "Lite-On"))
      (libsource (lib "MY_INT_LIB") (part "LTV-357T"))
    )
    (comp (ref "U21")
      (value "LTV-357T")
      (footprint "SMD-4")
      (description "Transistor Output Optocouplers Optocoupler Phototrans")
      (fields (field (name "MANUFACTURER") "Lite-On"))
      (libsource (lib "MY_INT_LIB") (part "LTV-357T"))
    )
    (comp (ref "U22")
      (value "LTV-357T")
      (footprint "SMD-4")
      (description "Transistor Output Optocouplers Optocoupler Phototrans")
      (fields (field (name "MANUFACTURER") "Lite-On"))
      (libsource (lib "MY_INT_LIB") (part "LTV-357T"))
    )
    (comp (ref "U23")
      (value "LTV-357T")
      (footprint "SMD-4")
      (description "Transistor Output Optocouplers Optocoupler Phototrans")
      (fields (field (name "MANUFACTURER") "Lite-On"))
      (libsource (lib "MY_INT_LIB") (part "LTV-357T"))
    )
    (comp (ref "U24")
      (value "LTV-357T")
      (footprint "SMD-4")
      (description "Transistor Output Optocouplers Optocoupler Phototrans")
      (fields (field (name "MANUFACTURER") "Lite-On"))
      (libsource (lib "MY_INT_LIB") (part "LTV-357T"))
    )
    (comp (ref "U25")
      (value "LTV-357T")
      (footprint "SMD-4")
      (description "Transistor Output Optocouplers Optocoupler Phototrans")
      (fields (field (name "MANUFACTURER") "Lite-On"))
      (libsource (lib "MY_INT_LIB") (part "LTV-357T"))
    )
    (comp (ref "U34")
      (value "CD74HC4067M96")
      (footprint "SOIC-24")
      (description "1 MHz, Low-Power Op Amp")
      (fields (field (name "MANUFACTURER") "Texas Instruments"))
      (libsource (lib "MY_INT_LIB") (part "CD74HC4067M96"))
    )
    (comp (ref "U35") (value "74HC595") (footprint "74HC595") (libsource (lib "74HC595") (part "74HC595")))
    (comp (ref "U36") (value "74HC595") (footprint "74HC595") (libsource (lib "74HC595") (part "74HC595")))
    (comp (ref "VD1")
      (value "1N4148W-7-F")
      (footprint "SOD-123")
      (description "Diodes - General Purpose, Power, Switching SURFACE MOUNT FAST SWITCHING DIODE")
      (fields (field (name "MANUFACTURER") "Diodes Incorporated"))
      (libsource (lib "MY_INT_LIB") (part "1N4148W-7-F"))
    )
    (comp (ref "VD2")
      (value "1N4148W-7-F")
      (footprint "SOD-123")
      (description "Diodes - General Purpose, Power, Switching SURFACE MOUNT FAST SWITCHING DIODE")
      (fields (field (name "MANUFACTURER") "Diodes Incorporated"))
      (libsource (lib "MY_INT_LIB") (part "1N4148W-7-F"))
    )
    (comp (ref "VD3")
      (value "1N4148W-7-F")
      (footprint "SOD-123")
      (description "Diodes - General Purpose, Power, Switching SURFACE MOUNT FAST SWITCHING DIODE")
      (fields (field (name "MANUFACTURER") "Diodes Incorporated"))
      (libsource (lib "MY_INT_LIB") (part "1N4148W-7-F"))
    )
    (comp (ref "VD4")
      (value "1N4148W-7-F")
      (footprint "SOD-123")
      (description "Diodes - General Purpose, Power, Switching SURFACE MOUNT FAST SWITCHING DIODE")
      (fields (field (name "MANUFACTURER") "Diodes Incorporated"))
      (libsource (lib "MY_INT_LIB") (part "1N4148W-7-F"))
    )
    (comp (ref "VD5")
      (value "1N4148W-7-F")
      (footprint "SOD-123")
      (description "Diodes - General Purpose, Power, Switching SURFACE MOUNT FAST SWITCHING DIODE")
      (fields (field (name "MANUFACTURER") "Diodes Incorporated"))
      (libsource (lib "MY_INT_LIB") (part "1N4148W-7-F"))
    )
    (comp (ref "VD6")
      (value "1N4148W-7-F")
      (footprint "SOD-123")
      (description "Diodes - General Purpose, Power, Switching SURFACE MOUNT FAST SWITCHING DIODE")
      (fields (field (name "MANUFACTURER") "Diodes Incorporated"))
      (libsource (lib "MY_INT_LIB") (part "1N4148W-7-F"))
    )
    (comp (ref "VD7")
      (value "1N4148W-7-F")
      (footprint "SOD-123")
      (description "Diodes - General Purpose, Power, Switching SURFACE MOUNT FAST SWITCHING DIODE")
      (fields (field (name "MANUFACTURER") "Diodes Incorporated"))
      (libsource (lib "MY_INT_LIB") (part "1N4148W-7-F"))
    )
    (comp (ref "VD8")
      (value "1N4148W-7-F")
      (footprint "SOD-123")
      (description "Diodes - General Purpose, Power, Switching SURFACE MOUNT FAST SWITCHING DIODE")
      (fields (field (name "MANUFACTURER") "Diodes Incorporated"))
      (libsource (lib "MY_INT_LIB") (part "1N4148W-7-F"))
    )
    (comp (ref "VD9")
      (value "1N4148W-7-F")
      (footprint "SOD-123")
      (description "Diodes - General Purpose, Power, Switching SURFACE MOUNT FAST SWITCHING DIODE")
      (fields (field (name "MANUFACTURER") "Diodes Incorporated"))
      (libsource (lib "MY_INT_LIB") (part "1N4148W-7-F"))
    )
    (comp (ref "VD10")
      (value "1N4148W-7-F")
      (footprint "SOD-123")
      (description "Diodes - General Purpose, Power, Switching SURFACE MOUNT FAST SWITCHING DIODE")
      (fields (field (name "MANUFACTURER") "Diodes Incorporated"))
      (libsource (lib "MY_INT_LIB") (part "1N4148W-7-F"))
    )
    (comp (ref "VD11")
      (value "1N4148W-7-F")
      (footprint "SOD-123")
      (description "Diodes - General Purpose, Power, Switching SURFACE MOUNT FAST SWITCHING DIODE")
      (fields (field (name "MANUFACTURER") "Diodes Incorporated"))
      (libsource (lib "MY_INT_LIB") (part "1N4148W-7-F"))
    )
    (comp (ref "VD12")
      (value "1N4148W-7-F")
      (footprint "SOD-123")
      (description "Diodes - General Purpose, Power, Switching SURFACE MOUNT FAST SWITCHING DIODE")
      (fields (field (name "MANUFACTURER") "Diodes Incorporated"))
      (libsource (lib "MY_INT_LIB") (part "1N4148W-7-F"))
    )
    (comp (ref "VD13")
      (value "1N4148W-7-F")
      (footprint "SOD-123")
      (description "Diodes - General Purpose, Power, Switching SURFACE MOUNT FAST SWITCHING DIODE")
      (fields (field (name "MANUFACTURER") "Diodes Incorporated"))
      (libsource (lib "MY_INT_LIB") (part "1N4148W-7-F"))
    )
    (comp (ref "VD14")
      (value "1N4148W-7-F")
      (footprint "SOD-123")
      (description "Diodes - General Purpose, Power, Switching SURFACE MOUNT FAST SWITCHING DIODE")
      (fields (field (name "MANUFACTURER") "Diodes Incorporated"))
      (libsource (lib "MY_INT_LIB") (part "1N4148W-7-F"))
    )
    (comp (ref "VD15")
      (value "1N4148W-7-F")
      (footprint "SOD-123")
      (description "Diodes - General Purpose, Power, Switching SURFACE MOUNT FAST SWITCHING DIODE")
      (fields (field (name "MANUFACTURER") "Diodes Incorporated"))
      (libsource (lib "MY_INT_LIB") (part "1N4148W-7-F"))
    )
    (comp (ref "VD16")
      (value "1N4148W-7-F")
      (footprint "SOD-123")
      (description "Diodes - General Purpose, Power, Switching SURFACE MOUNT FAST SWITCHING DIODE")
      (fields (field (name "MANUFACTURER") "Diodes Incorporated"))
      (libsource (lib "MY_INT_LIB") (part "1N4148W-7-F"))
    )
    (comp (ref "VD17")
      (value "1N4148W-7-F")
      (footprint "SOD-123")
      (description "Diodes - General Purpose, Power, Switching SURFACE MOUNT FAST SWITCHING DIODE")
      (fields (field (name "MANUFACTURER") "Diodes Incorporated"))
      (libsource (lib "MY_INT_LIB") (part "1N4148W-7-F"))
    )
    (comp (ref "VD18")
      (value "1N4148W-7-F")
      (footprint "SOD-123")
      (description "Diodes - General Purpose, Power, Switching SURFACE MOUNT FAST SWITCHING DIODE")
      (fields (field (name "MANUFACTURER") "Diodes Incorporated"))
      (libsource (lib "MY_INT_LIB") (part "1N4148W-7-F"))
    )
    (comp (ref "VD19")
      (value "1N4148W-7-F")
      (footprint "SOD-123")
      (description "Diodes - General Purpose, Power, Switching SURFACE MOUNT FAST SWITCHING DIODE")
      (fields (field (name "MANUFACTURER") "Diodes Incorporated"))
      (libsource (lib "MY_INT_LIB") (part "1N4148W-7-F"))
    )
    (comp (ref "VD20")
      (value "1N4148W-7-F")
      (footprint "SOD-123")
      (description "Diodes - General Purpose, Power, Switching SURFACE MOUNT FAST SWITCHING DIODE")
      (fields (field (name "MANUFACTURER") "Diodes Incorporated"))
      (libsource (lib "MY_INT_LIB") (part "1N4148W-7-F"))
    )
    (comp (ref "VD21")
      (value "1N4148W-7-F")
      (footprint "SOD-123")
      (description "Diodes - General Purpose, Power, Switching SURFACE MOUNT FAST SWITCHING DIODE")
      (fields (field (name "MANUFACTURER") "Diodes Incorporated"))
      (libsource (lib "MY_INT_LIB") (part "1N4148W-7-F"))
    )
    (comp (ref "VD22")
      (value "1N4148W-7-F")
      (footprint "SOD-123")
      (description "Diodes - General Purpose, Power, Switching SURFACE MOUNT FAST SWITCHING DIODE")
      (fields (field (name "MANUFACTURER") "Diodes Incorporated"))
      (libsource (lib "MY_INT_LIB") (part "1N4148W-7-F"))
    )
    (comp (ref "VD23")
      (value "1N4148W-7-F")
      (footprint "SOD-123")
      (description "Diodes - General Purpose, Power, Switching SURFACE MOUNT FAST SWITCHING DIODE")
      (fields (field (name "MANUFACTURER") "Diodes Incorporated"))
      (libsource (lib "MY_INT_LIB") (part "1N4148W-7-F"))
    )
    (comp (ref "VD24")
      (value "1N4148W-7-F")
      (footprint "SOD-123")
      (description "Diodes - General Purpose, Power, Switching SURFACE MOUNT FAST SWITCHING DIODE")
      (fields (field (name "MANUFACTURER") "Diodes Incorporated"))
      (libsource (lib "MY_INT_LIB") (part "1N4148W-7-F"))
    )
    (comp (ref "VT1")
      (value "2N7002(NX7002AK)")
      (footprint "SOT-23-3")
      (description "MOSFET N-CHANNEL 60V 115mA")
      (fields (field (name "MANUFACTURER") "Fairchild"))
      (libsource (lib "MY_INT_LIB") (part "2N7002"))
    )
    (comp (ref "VT2")
      (value "2N7002(NX7002AK)")
      (footprint "SOT-23-3")
      (description "MOSFET N-CHANNEL 60V 115mA")
      (fields (field (name "MANUFACTURER") "Fairchild"))
      (libsource (lib "MY_INT_LIB") (part "2N7002"))
    )
    (comp (ref "VT3")
      (value "2N7002(NX7002AK)")
      (footprint "SOT-23-3")
      (description "MOSFET N-CHANNEL 60V 115mA")
      (fields (field (name "MANUFACTURER") "Fairchild"))
      (libsource (lib "MY_INT_LIB") (part "2N7002"))
    )
    (comp (ref "VT4")
      (value "2N7002(NX7002AK)")
      (footprint "SOT-23-3")
      (description "MOSFET N-CHANNEL 60V 115mA")
      (fields (field (name "MANUFACTURER") "Fairchild"))
      (libsource (lib "MY_INT_LIB") (part "2N7002"))
    )
    (comp (ref "VT5")
      (value "2N7002(NX7002AK)")
      (footprint "SOT-23-3")
      (description "MOSFET N-CHANNEL 60V 115mA")
      (fields (field (name "MANUFACTURER") "Fairchild"))
      (libsource (lib "MY_INT_LIB") (part "2N7002"))
    )
    (comp (ref "VT6")
      (value "2N7002(NX7002AK)")
      (footprint "SOT-23-3")
      (description "MOSFET N-CHANNEL 60V 115mA")
      (fields (field (name "MANUFACTURER") "Fairchild"))
      (libsource (lib "MY_INT_LIB") (part "2N7002"))
    )
    (comp (ref "VT7")
      (value "2N7002(NX7002AK)")
      (footprint "SOT-23-3")
      (description "MOSFET N-CHANNEL 60V 115mA")
      (fields (field (name "MANUFACTURER") "Fairchild"))
      (libsource (lib "MY_INT_LIB") (part "2N7002"))
    )
    (comp (ref "VT8")
      (value "2N7002(NX7002AK)")
      (footprint "SOT-23-3")
      (description "MOSFET N-CHANNEL 60V 115mA")
      (fields (field (name "MANUFACTURER") "Fairchild"))
      (libsource (lib "MY_INT_LIB") (part "2N7002"))
    )
    (comp (ref "VT9")
      (value "2N7002(NX7002AK)")
      (footprint "SOT-23-3")
      (description "MOSFET N-CHANNEL 60V 115mA")
      (fields (field (name "MANUFACTURER") "Fairchild"))
      (libsource (lib "MY_INT_LIB") (part "2N7002"))
    )
    (comp (ref "VT10")
      (value "2N7002(NX7002AK)")
      (footprint "SOT-23-3")
      (description "MOSFET N-CHANNEL 60V 115mA")
      (fields (field (name "MANUFACTURER") "Fairchild"))
      (libsource (lib "MY_INT_LIB") (part "2N7002"))
    )
    (comp (ref "VT11")
      (value "2N7002(NX7002AK)")
      (footprint "SOT-23-3")
      (description "MOSFET N-CHANNEL 60V 115mA")
      (fields (field (name "MANUFACTURER") "Fairchild"))
      (libsource (lib "MY_INT_LIB") (part "2N7002"))
    )
    (comp (ref "VT12")
      (value "2N7002(NX7002AK)")
      (footprint "SOT-23-3")
      (description "MOSFET N-CHANNEL 60V 115mA")
      (fields (field (name "MANUFACTURER") "Fairchild"))
      (libsource (lib "MY_INT_LIB") (part "2N7002"))
    )
    (comp (ref "VT13")
      (value "2N7002(NX7002AK)")
      (footprint "SOT-23-3")
      (description "MOSFET N-CHANNEL 60V 115mA")
      (fields (field (name "MANUFACTURER") "Fairchild"))
      (libsource (lib "MY_INT_LIB") (part "2N7002"))
    )
    (comp (ref "VT14")
      (value "2N7002(NX7002AK)")
      (footprint "SOT-23-3")
      (description "MOSFET N-CHANNEL 60V 115mA")
      (fields (field (name "MANUFACTURER") "Fairchild"))
      (libsource (lib "MY_INT_LIB") (part "2N7002"))
    )
    (comp (ref "VT15")
      (value "2N7002(NX7002AK)")
      (footprint "SOT-23-3")
      (description "MOSFET N-CHANNEL 60V 115mA")
      (fields (field (name "MANUFACTURER") "Fairchild"))
      (libsource (lib "MY_INT_LIB") (part "2N7002"))
    )
    (comp (ref "VT16")
      (value "2N7002(NX7002AK)")
      (footprint "SOT-23-3")
      (description "MOSFET N-CHANNEL 60V 115mA")
      (fields (field (name "MANUFACTURER") "Fairchild"))
      (libsource (lib "MY_INT_LIB") (part "2N7002"))
    )
    (comp (ref "VT17")
      (value "2N7002(NX7002AK)")
      (footprint "SOT-23-3")
      (description "MOSFET N-CHANNEL 60V 115mA")
      (fields (field (name "MANUFACTURER") "Fairchild"))
      (libsource (lib "MY_INT_LIB") (part "2N7002"))
    )
    (comp (ref "VT18")
      (value "2N7002(NX7002AK)")
      (footprint "SOT-23-3")
      (description "MOSFET N-CHANNEL 60V 115mA")
      (fields (field (name "MANUFACTURER") "Fairchild"))
      (libsource (lib "MY_INT_LIB") (part "2N7002"))
    )
    (comp (ref "VT19")
      (value "2N7002(NX7002AK)")
      (footprint "SOT-23-3")
      (description "MOSFET N-CHANNEL 60V 115mA")
      (fields (field (name "MANUFACTURER") "Fairchild"))
      (libsource (lib "MY_INT_LIB") (part "2N7002"))
    )
    (comp (ref "VT20")
      (value "2N7002(NX7002AK)")
      (footprint "SOT-23-3")
      (description "MOSFET N-CHANNEL 60V 115mA")
      (fields (field (name "MANUFACTURER") "Fairchild"))
      (libsource (lib "MY_INT_LIB") (part "2N7002"))
    )
    (comp (ref "VT21")
      (value "2N7002(NX7002AK)")
      (footprint "SOT-23-3")
      (description "MOSFET N-CHANNEL 60V 115mA")
      (fields (field (name "MANUFACTURER") "Fairchild"))
      (libsource (lib "MY_INT_LIB") (part "2N7002"))
    )
    (comp (ref "VT22")
      (value "2N7002(NX7002AK)")
      (footprint "SOT-23-3")
      (description "MOSFET N-CHANNEL 60V 115mA")
      (fields (field (name "MANUFACTURER") "Fairchild"))
      (libsource (lib "MY_INT_LIB") (part "2N7002"))
    )
    (comp (ref "VT23")
      (value "2N7002(NX7002AK)")
      (footprint "SOT-23-3")
      (description "MOSFET N-CHANNEL 60V 115mA")
      (fields (field (name "MANUFACTURER") "Fairchild"))
      (libsource (lib "MY_INT_LIB") (part "2N7002"))
    )
    (comp (ref "VT24")
      (value "2N7002(NX7002AK)")
      (footprint "SOT-23-3")
      (description "MOSFET N-CHANNEL 60V 115mA")
      (fields (field (name "MANUFACTURER") "Fairchild"))
      (libsource (lib "MY_INT_LIB") (part "2N7002"))
    )
    (comp (ref "XP1")
      (value "DRB-37FA(DS1037-37F)")
      (footprint "DRB-37FA(DS1037-37F)")
      (description "Сonnector")
      (fields (field (name "MANUFACTURER") "Connfly"))
      (libsource (lib "MY_INT_LIB") (part "DRB-37FA(DS1037-37F)"))
    )
  )
  (nets
    (net (code "1") (name "+3V3") (class "Default")
      (node (ref "U34") (pin "24") (pinfunction "VCC_24") (pintype "power_in"))
      (node (ref "U35") (pin "10") (pinfunction "MR_10") (pintype "power_in"))
      (node (ref "U35") (pin "16") (pinfunction "VCC_16") (pintype "power_in"))
      (node (ref "U36") (pin "10") (pinfunction "MR_10") (pintype "power_in"))
      (node (ref "U36") (pin "16") (pinfunction "VCC_16") (pintype "power_in"))
    )
    (net (code "2") (name "+12V") (class "Default")
      (node (ref "C1") (pin "2") (pinfunction "2_2") (pintype "passive"))
      (node (ref "K1") (pin "2") (pinfunction "A2_2") (pintype "passive"))
      (node (ref "K10") (pin "2") (pinfunction "A2_2") (pintype "passive"))
      (node (ref "K11") (pin "2") (pinfunction "A2_2") (pintype "passive"))
      (node (ref "K12") (pin "2") (pinfunction "A2_2") (pintype "passive"))
      (node (ref "K13") (pin "2") (pinfunction "A2_2") (pintype "passive"))
      (node (ref "K14") (pin "2") (pinfunction "A2_2") (pintype "passive"))
      (node (ref "K15") (pin "2") (pinfunction "A2_2") (pintype "passive"))
      (node (ref "K16") (pin "2") (pinfunction "A2_2") (pintype "passive"))
      (node (ref "K17") (pin "2") (pinfunction "A2_2") (pintype "passive"))
      (node (ref "K18") (pin "2") (pinfunction "A2_2") (pintype "passive"))
      (node (ref "K19") (pin "2") (pinfunction "A2_2") (pintype "passive"))
      (node (ref "K2") (pin "2") (pinfunction "A2_2") (pintype "passive"))
      (node (ref "K20") (pin "2") (pinfunction "A2_2") (pintype "passive"))
      (node (ref "K21") (pin "2") (pinfunction "A2_2") (pintype "passive"))
      (node (ref "K22") (pin "2") (pinfunction "A2_2") (pintype "passive"))
      (node (ref "K23") (pin "2") (pinfunction "A2_2") (pintype "passive"))
      (node (ref "K24") (pin "2") (pinfunction "A2_2") (pintype "passive"))
      (node (ref "K3") (pin "2") (pinfunction "A2_2") (pintype "passive"))
      (node (ref "K4") (pin "2") (pinfunction "A2_2") (pintype "passive"))
      (node (ref "K5") (pin "2") (pinfunction "A2_2") (pintype "passive"))
      (node (ref "K6") (pin "2") (pinfunction "A2_2") (pintype "passive"))
      (node (ref "K7") (pin "2") (pinfunction "A2_2") (pintype "passive"))
      (node (ref "K8") (pin "2") (pinfunction "A2_2") (pintype "passive"))
      (node (ref "K9") (pin "2") (pinfunction "A2_2") (pintype "passive"))
      (node (ref "U1") (pin "4") (pintype "passive"))
      (node (ref "U10") (pin "4") (pintype "passive"))
      (node (ref "U11") (pin "4") (pintype "passive"))
      (node (ref "U12") (pin "4") (pintype "passive"))
      (node (ref "U13") (pin "4") (pintype "passive"))
      (node (ref "U14") (pin "4") (pintype "passive"))
      (node (ref "U15") (pin "4") (pintype "passive"))
      (node (ref "U16") (pin "4") (pintype "passive"))
      (node (ref "U17") (pin "1") (pinfunction "+V_inp_1") (pintype "passive"))
      (node (ref "U18") (pin "4") (pintype "passive"))
      (node (ref "U19") (pin "4") (pintype "passive"))
      (node (ref "U2") (pin "4") (pintype "passive"))
      (node (ref "U20") (pin "4") (pintype "passive"))
      (node (ref "U21") (pin "4") (pintype "passive"))
      (node (ref "U22") (pin "4") (pintype "passive"))
      (node (ref "U23") (pin "4") (pintype "passive"))
      (node (ref "U24") (pin "4") (pintype "passive"))
      (node (ref "U25") (pin "4") (pintype "passive"))
      (node (ref "U3") (pin "4") (pintype "passive"))
      (node (ref "U4") (pin "4") (pintype "passive"))
      (node (ref "U5") (pin "4") (pintype "passive"))
      (node (ref "U6") (pin "4") (pintype "passive"))
      (node (ref "U7") (pin "4") (pintype "passive"))
      (node (ref "U8") (pin "4") (pintype "passive"))
      (node (ref "U9") (pin "4") (pintype "passive"))
      (node (ref "VD1") (pin "1") (pintype "passive"))
      (node (ref "VD10") (pin "1") (pintype "passive"))
      (node (ref "VD11") (pin "1") (pintype "passive"))
      (node (ref "VD12") (pin "1") (pintype "passive"))
      (node (ref "VD13") (pin "1") (pintype "passive"))
      (node (ref "VD14") (pin "1") (pintype "passive"))
      (node (ref "VD15") (pin "1") (pintype "passive"))
      (node (ref "VD16") (pin "1") (pintype "passive"))
      (node (ref "VD17") (pin "1") (pintype "passive"))
      (node (ref "VD18") (pin "1") (pintype "passive"))
      (node (ref "VD19") (pin "1") (pintype "passive"))
      (node (ref "VD2") (pin "1") (pintype "passive"))
      (node (ref "VD20") (pin "1") (pintype "passive"))
      (node (ref "VD21") (pin "1") (pintype "passive"))
      (node (ref "VD22") (pin "1") (pintype "passive"))
      (node (ref "VD23") (pin "1") (pintype "passive"))
      (node (ref "VD24") (pin "1") (pintype "passive"))
      (node (ref "VD3") (pin "1") (pintype "passive"))
      (node (ref "VD4") (pin "1") (pintype "passive"))
      (node (ref "VD5") (pin "1") (pintype "passive"))
      (node (ref "VD6") (pin "1") (pintype "passive"))
      (node (ref "VD7") (pin "1") (pintype "passive"))
      (node (ref "VD8") (pin "1") (pintype "passive"))
      (node (ref "VD9") (pin "1") (pintype "passive"))
    )
    (net (code "3") (name "+12V_CLEAR") (class "Default")
      (node (ref "C2") (pin "2") (pinfunction "2_2") (pintype "passive"))
      (node (ref "U17") (pin "3") (pinfunction "+V_out_3") (pintype "passive"))
    )
    (net (code "4") (name "/E.GND1") (class "Default")
      (node (ref "XP1") (pin "9") (pinfunction "A9_9") (pintype "passive"))
    )
    (net (code "5") (name "/E.GND2") (class "Default")
      (node (ref "XP1") (pin "28") (pinfunction "B9_28") (pintype "passive"))
    )
    (net (code "6") (name "/GPIO_TU_1") (class "Default")
      (node (ref "U35") (pin "15") (pinfunction "Q0_15") (pintype "power_in"))
    )
    (net (code "7") (name "/GPIO_TU_2") (class "Default")
      (node (ref "U35") (pin "1") (pinfunction "Q1_1") (pintype "power_in"))
    )
    (net (code "8") (name "/GPIO_TU_3") (class "Default")
      (node (ref "U35") (pin "2") (pinfunction "Q2_2") (pintype "power_in"))
    )
    (net (code "9") (name "/GPIO_TU_4") (class "Default")
      (node (ref "U35") (pin "3") (pinfunction "Q3_3") (pintype "power_in"))
    )
    (net (code "10") (name "/GPIO_TU_5") (class "Default")
      (node (ref "U35") (pin "4") (pinfunction "Q4_4") (pintype "power_in"))
    )
    (net (code "11") (name "/GPIO_TU_6") (class "Default")
      (node (ref "U35") (pin "5") (pinfunction "Q5_5") (pintype "power_in"))
    )
    (net (code "12") (name "/GPIO_TU_7") (class "Default")
      (node (ref "U35") (pin "6") (pinfunction "Q6_6") (pintype "power_in"))
    )
    (net (code "13") (name "/GPIO_TU_8") (class "Default")
      (node (ref "U35") (pin "7") (pinfunction "Q7_7") (pintype "power_in"))
    )
    (net (code "14") (name "/GPIO_TU_9") (class "Default")
      (node (ref "U36") (pin "15") (pinfunction "Q0_15") (pintype "power_in"))
    )
    (net (code "15") (name "/GPIO_TU_10") (class "Default")
      (node (ref "U36") (pin "1") (pinfunction "Q1_1") (pintype "power_in"))
    )
    (net (code "16") (name "/GPIO_TU_11") (class "Default")
      (node (ref "U36") (pin "2") (pinfunction "Q2_2") (pintype "power_in"))
    )
    (net (code "17") (name "/GPIO_TU_12") (class "Default")
      (node (ref "U36") (pin "3") (pinfunction "Q3_3") (pintype "power_in"))
    )
    (net (code "18") (name "/GPIO_TU_13") (class "Default")
      (node (ref "U36") (pin "4") (pinfunction "Q4_4") (pintype "power_in"))
    )
    (net (code "19") (name "/GPIO_TU_14") (class "Default")
      (node (ref "U36") (pin "5") (pinfunction "Q5_5") (pintype "power_in"))
    )
    (net (code "20") (name "/GPIO_TU_15") (class "Default")
      (node (ref "U36") (pin "6") (pinfunction "Q6_6") (pintype "power_in"))
    )
    (net (code "21") (name "/GPIO_TU_16") (class "Default")
      (node (ref "U36") (pin "7") (pinfunction "Q7_7") (pintype "power_in"))
    )
    (net (code "22") (name "/I0") (class "Default")
      (node (ref "U34") (pin "9") (pinfunction "I_0_9") (pintype "passive"))
    )
    (net (code "23") (name "/I1") (class "Default")
      (node (ref "U34") (pin "8") (pinfunction "I_1_8") (pintype "passive"))
    )
    (net (code "24") (name "/I2") (class "Default")
      (node (ref "U34") (pin "7") (pinfunction "I_2_7") (pintype "passive"))
    )
    (net (code "25") (name "/I3") (class "Default")
      (node (ref "U34") (pin "6") (pinfunction "I_3_6") (pintype "passive"))
    )
    (net (code "26") (name "/I4") (class "Default")
      (node (ref "U34") (pin "5") (pinfunction "I_4_5") (pintype "passive"))
    )
    (net (code "27") (name "/I5") (class "Default")
      (node (ref "U34") (pin "4") (pinfunction "I_5_4") (pintype "passive"))
    )
    (net (code "28") (name "/I6") (class "Default")
      (node (ref "U34") (pin "3") (pinfunction "I_6_3") (pintype "passive"))
    )
    (net (code "29") (name "/I7") (class "Default")
      (node (ref "U34") (pin "2") (pinfunction "I_7_2") (pintype "passive"))
    )
    (net (code "30") (name "/I8") (class "Default")
      (node (ref "U34") (pin "23") (pinfunction "I_8_23") (pintype "passive"))
    )
    (net (code "31") (name "/I9") (class "Default")
      (node (ref "U34") (pin "22") (pinfunction "I_9_22") (pintype "passive"))
    )
    (net (code "32") (name "/I10") (class "Default")
      (node (ref "U34") (pin "21") (pinfunction "I_10_21") (pintype "passive"))
    )
    (net (code "33") (name "/I11") (class "Default")
      (node (ref "U34") (pin "20") (pinfunction "I_11_20") (pintype "passive"))
    )
    (net (code "34") (name "/I12") (class "Default")
      (node (ref "U34") (pin "19") (pinfunction "I_12_19") (pintype "passive"))
    )
    (net (code "35") (name "/I13") (class "Default")
      (node (ref "U34") (pin "18") (pinfunction "I_13_18") (pintype "passive"))
    )
    (net (code "36") (name "/I14") (class "Default")
      (node (ref "U34") (pin "17") (pinfunction "I_14_17") (pintype "passive"))
    )
    (net (code "37") (name "/I15") (class "Default")
      (node (ref "U34") (pin "16") (pinfunction "I_15_16") (pintype "passive"))
    )
    (net (code "38") (name "/IDI_0") (class "Default")
      (node (ref "XP1") (pin "1") (pinfunction "A1_1") (pintype "passive"))
    )
    (net (code "39") (name "/IDI_1") (class "Default")
      (node (ref "XP1") (pin "20") (pinfunction "B1_20") (pintype "passive"))
    )
    (net (code "40") (name "/IDI_2") (class "Default")
      (node (ref "XP1") (pin "2") (pinfunction "A2_2") (pintype "passive"))
    )
    (net (code "41") (name "/IDI_3") (class "Default")
      (node (ref "XP1") (pin "21") (pinfunction "B2_21") (pintype "passive"))
    )
    (net (code "42") (name "/IDI_4") (class "Default")
      (node (ref "XP1") (pin "3") (pinfunction "A3_3") (pintype "passive"))
    )
    (net (code "43") (name "/IDI_5") (class "Default")
      (node (ref "XP1") (pin "22") (pinfunction "B3_22") (pintype "passive"))
    )
    (net (code "44") (name "/IDI_6") (class "Default")
      (node (ref "XP1") (pin "4") (pinfunction "A4_4") (pintype "passive"))
    )
    (net (code "45") (name "/IDI_7") (class "Default")
      (node (ref "XP1") (pin "23") (pinfunction "B4_23") (pintype "passive"))
    )
    (net (code "46") (name "/IDI_8") (class "Default")
      (node (ref "XP1") (pin "5") (pinfunction "A5_5") (pintype "passive"))
    )
    (net (code "47") (name "/IDI_9") (class "Default")
      (node (ref "XP1") (pin "24") (pinfunction "B5_24") (pintype "passive"))
    )
    (net (code "48") (name "/IDI_10") (class "Default")
      (node (ref "XP1") (pin "6") (pinfunction "A6_6") (pintype "passive"))
    )
    (net (code "49") (name "/IDI_11") (class "Default")
      (node (ref "XP1") (pin "25") (pinfunction "B6_25") (pintype "passive"))
    )
    (net (code "50") (name "/IDI_12") (class "Default")
      (node (ref "XP1") (pin "7") (pinfunction "A7_7") (pintype "passive"))
    )
    (net (code "51") (name "/IDI_13") (class "Default")
      (node (ref "XP1") (pin "26") (pinfunction "B7_26") (pintype "passive"))
    )
    (net (code "52") (name "/IDI_14") (class "Default")
      (node (ref "XP1") (pin "8") (pinfunction "A8_8") (pintype "passive"))
    )
    (net (code "53") (name "/IDI_15") (class "Default")
      (node (ref "XP1") (pin "27") (pinfunction "B8_27") (pintype "passive"))
    )
    (net (code "54") (name "/IDO_0") (class "Default")
      (node (ref "XP1") (pin "11") (pinfunction "A11_11") (pintype "passive"))
    )
    (net (code "55") (name "/IDO_1") (class "Default")
      (node (ref "XP1") (pin "30") (pinfunction "B11_30") (pintype "passive"))
    )
    (net (code "56") (name "/IDO_2") (class "Default")
      (node (ref "XP1") (pin "12") (pinfunction "A12_12") (pintype "passive"))
    )
    (net (code "57") (name "/IDO_3") (class "Default")
      (node (ref "XP1") (pin "31") (pinfunction "B12_31") (pintype "passive"))
    )
    (net (code "58") (name "/IDO_4") (class "Default")
      (node (ref "XP1") (pin "13") (pinfunction "A13_13") (pintype "passive"))
    )
    (net (code "59") (name "/IDO_5") (class "Default")
      (node (ref "XP1") (pin "32") (pinfunction "B13_32") (pintype "passive"))
    )
    (net (code "60") (name "/IDO_6") (class "Default")
      (node (ref "XP1") (pin "14") (pinfunction "A14_14") (pintype "passive"))
    )
    (net (code "61") (name "/IDO_7") (class "Default")
      (node (ref "XP1") (pin "33") (pinfunction "B14_33") (pintype "passive"))
    )
    (net (code "62") (name "/IDO_8") (class "Default")
      (node (ref "XP1") (pin "15") (pinfunction "A15_15") (pintype "passive"))
    )
    (net (code "63") (name "/IDO_9") (class "Default")
      (node (ref "XP1") (pin "34") (pinfunction "B15_34") (pintype "passive"))
    )
    (net (code "64") (name "/IDO_10") (class "Default")
      (node (ref "XP1") (pin "16") (pinfunction "A16_16") (pintype "passive"))
    )
    (net (code "65") (name "/IDO_11") (class "Default")
      (node (ref "XP1") (pin "35") (pinfunction "B16_35") (pintype "passive"))
    )
    (net (code "66") (name "/IDO_12") (class "Default")
      (node (ref "XP1") (pin "17") (pinfunction "A17_17") (pintype "passive"))
    )
    (net (code "67") (name "/IDO_13") (class "Default")
      (node (ref "XP1") (pin "36") (pinfunction "B17_36") (pintype "passive"))
    )
    (net (code "68") (name "/IDO_14") (class "Default")
      (node (ref "XP1") (pin "18") (pinfunction "A18_18") (pintype "passive"))
    )
    (net (code "69") (name "/IDO_15") (class "Default")
      (node (ref "XP1") (pin "37") (pinfunction "B18_37") (pintype "passive"))
    )
    (net (code "70") (name "/OUT_1") (class "Default")
      (node (ref "K1") (pin "5") (pinfunction "NO_5") (pintype "passive"))
    )
    (net (code "71") (name "/OUT_2") (class "Default")
      (node (ref "K2") (pin "5") (pinfunction "NO_5") (pintype "passive"))
    )
    (net (code "72") (name "/OUT_3") (class "Default")
      (node (ref "K3") (pin "5") (pinfunction "NO_5") (pintype "passive"))
    )
    (net (code "73") (name "/OUT_4") (class "Default")
      (node (ref "K4") (pin "5") (pinfunction "NO_5") (pintype "passive"))
    )
    (net (code "74") (name "/OUT_5") (class "Default")
      (node (ref "K5") (pin "5") (pinfunction "NO_5") (pintype "passive"))
    )
    (net (code "75") (name "/OUT_6") (class "Default")
      (node (ref "K6") (pin "5") (pinfunction "NO_5") (pintype "passive"))
    )
    (net (code "76") (name "/OUT_7") (class "Default")
      (node (ref "K7") (pin "5") (pinfunction "NO_5") (pintype "passive"))
    )
    (net (code "77") (name "/OUT_8") (class "Default")
      (node (ref "K8") (pin "5") (pinfunction "NO_5") (pintype "passive"))
    )
    (net (code "78") (name "/OUT_9") (class "Default")
      (node (ref "K9") (pin "5") (pinfunction "NO_5") (pintype "passive"))
    )
    (net (code "79") (name "/OUT_10") (class "Default")
      (node (ref "K10") (pin "5") (pinfunction "NO_5") (pintype "passive"))
    )
    (net (code "80") (name "/OUT_11") (class "Default")
      (node (ref "K11") (pin "5") (pinfunction "NO_5") (pintype "passive"))
    )
    (net (code "81") (name "/OUT_12") (class "Default")
      (node (ref "K12") (pin "5") (pinfunction "NO_5") (pintype "passive"))
    )
    (net (code "82") (name "/OUT_13") (class "Default")
      (node (ref "K13") (pin "5") (pinfunction "NO_5") (pintype "passive"))
    )
    (net (code "83") (name "/OUT_14") (class "Default")
      (node (ref "K14") (pin "5") (pinfunction "NO_5") (pintype "passive"))
    )
    (net (code "84") (name "/OUT_15") (class "Default")
      (node (ref "K15") (pin "5") (pinfunction "NO_5") (pintype "passive"))
    )
    (net (code "85") (name "/OUT_16") (class "Default")
      (node (ref "K16") (pin "5") (pinfunction "NO_5") (pintype "passive"))
    )
    (net (code "86") (name "/OUT_17") (class "Default")
      (node (ref "K17") (pin "5") (pinfunction "NO_5") (pintype "passive"))
    )
    (net (code "87") (name "/OUT_18") (class "Default")
      (node (ref "K18") (pin "5") (pinfunction "NO_5") (pintype "passive"))
    )
    (net (code "88") (name "/OUT_19") (class "Default")
      (node (ref "K19") (pin "5") (pinfunction "NO_5") (pintype "passive"))
    )
    (net (code "89") (name "/OUT_20") (class "Default")
      (node (ref "K20") (pin "5") (pinfunction "NO_5") (pintype "passive"))
    )
    (net (code "90") (name "/OUT_21") (class "Default")
      (node (ref "K21") (pin "5") (pinfunction "NO_5") (pintype "passive"))
    )
    (net (code "91") (name "/OUT_22") (class "Default")
      (node (ref "K22") (pin "5") (pinfunction "NO_5") (pintype "passive"))
    )
    (net (code "92") (name "/OUT_23") (class "Default")
      (node (ref "K23") (pin "5") (pinfunction "NO_5") (pintype "passive"))
    )
    (net (code "93") (name "/OUT_24") (class "Default")
      (node (ref "K24") (pin "5") (pinfunction "NO_5") (pintype "passive"))
    )
    (net (code "94") (name "/OUT_COM") (class "Default")
      (node (ref "K1") (pin "4") (pinfunction "COM_4") (pintype "passive"))
      (node (ref "K10") (pin "4") (pinfunction "COM_4") (pintype "passive"))
      (node (ref "K11") (pin "4") (pinfunction "COM_4") (pintype "passive"))
      (node (ref "K12") (pin "4") (pinfunction "COM_4") (pintype "passive"))
      (node (ref "K13") (pin "4") (pinfunction "COM_4") (pintype "passive"))
      (node (ref "K14") (pin "4") (pinfunction "COM_4") (pintype "passive"))
      (node (ref "K15") (pin "4") (pinfunction "COM_4") (pintype "passive"))
      (node (ref "K16") (pin "4") (pinfunction "COM_4") (pintype "passive"))
      (node (ref "K17") (pin "4") (pinfunction "COM_4") (pintype "passive"))
      (node (ref "K18") (pin "4") (pinfunction "COM_4") (pintype "passive"))
      (node (ref "K19") (pin "4") (pinfunction "COM_4") (pintype "passive"))
      (node (ref "K2") (pin "4") (pinfunction "COM_4") (pintype "passive"))
      (node (ref "K20") (pin "4") (pinfunction "COM_4") (pintype "passive"))
      (node (ref "K21") (pin "4") (pinfunction "COM_4") (pintype "passive"))
      (node (ref "K22") (pin "4") (pinfunction "COM_4") (pintype "passive"))
      (node (ref "K23") (pin "4") (pinfunction "COM_4") (pintype "passive"))
      (node (ref "K24") (pin "4") (pinfunction "COM_4") (pintype "passive"))
      (node (ref "K3") (pin "4") (pinfunction "COM_4") (pintype "passive"))
      (node (ref "K4") (pin "4") (pinfunction "COM_4") (pintype "passive"))
      (node (ref "K5") (pin "4") (pinfunction "COM_4") (pintype "passive"))
      (node (ref "K6") (pin "4") (pinfunction "COM_4") (pintype "passive"))
      (node (ref "K7") (pin "4") (pinfunction "COM_4") (pintype "passive"))
      (node (ref "K8") (pin "4") (pinfunction "COM_4") (pintype "passive"))
      (node (ref "K9") (pin "4") (pinfunction "COM_4") (pintype "passive"))
    )
    (net (code "95") (name "/SPI1_CS1") (class "Default")
      (node (ref "R145") (pin "2") (pinfunction "2_2") (pintype "passive"))
      (node (ref "U35") (pin "12") (pinfunction "STCP_12") (pintype "power_in"))
    )
    (net (code "96") (name "/SPI1_CS2") (class "Default")
      (node (ref "R146") (pin "2") (pinfunction "2_2") (pintype "passive"))
      (node (ref "U36") (pin "12") (pinfunction "STCP_12") (pintype "power_in"))
    )
    (net (code "97") (name "/SPI1_MOSI") (class "Default")
      (node (ref "R148") (pin "2") (pinfunction "2_2") (pintype "passive"))
      (node (ref "U35") (pin "14") (pinfunction "DS_14") (pintype "power_in"))
      (node (ref "U36") (pin "14") (pinfunction "DS_14") (pintype "power_in"))
    )
    (net (code "98") (name "/SPI1_SCK") (class "Default")
      (node (ref "R147") (pin "2") (pinfunction "2_2") (pintype "passive"))
      (node (ref "U35") (pin "11") (pinfunction "SHCP_11") (pintype "power_in"))
      (node (ref "U36") (pin "11") (pinfunction "SHCP_11") (pintype "power_in"))
    )
    (net (code "99") (name "/S_0") (class "Default")
      (node (ref "U34") (pin "10") (pinfunction "S_0_10") (pintype "passive"))
    )
    (net (code "100") (name "/S_1") (class "Default")
      (node (ref "U34") (pin "11") (pinfunction "S_1_11") (pintype "passive"))
    )
    (net (code "101") (name "/S_2") (class "Default")
      (node (ref "U34") (pin "14") (pinfunction "S_2_14") (pintype "passive"))
    )
    (net (code "102") (name "/S_3") (class "Default")
      (node (ref "U34") (pin "13") (pinfunction "S_3_13") (pintype "passive"))
    )
    (net (code "103") (name "/TS_IN_COM") (class "Default")
      (node (ref "U34") (pin "1") (pinfunction "COM_I/O_1") (pintype "passive"))
    )
    (net (code "104") (name "/tu_1") (class "Default")
      (node (ref "R1") (pin "1") (pinfunction "1_1") (pintype "passive"))
      (node (ref "U1") (pin "1") (pintype "passive"))
    )
    (net (code "105") (name "/tu_2") (class "Default")
      (node (ref "R4") (pin "1") (pinfunction "1_1") (pintype "passive"))
      (node (ref "U2") (pin "1") (pintype "passive"))
    )
    (net (code "106") (name "/tu_3") (class "Default")
      (node (ref "R7") (pin "1") (pinfunction "1_1") (pintype "passive"))
      (node (ref "U3") (pin "1") (pintype "passive"))
    )
    (net (code "107") (name "/tu_4") (class "Default")
      (node (ref "R10") (pin "1") (pinfunction "1_1") (pintype "passive"))
      (node (ref "U4") (pin "1") (pintype "passive"))
    )
    (net (code "108") (name "/tu_5") (class "Default")
      (node (ref "R13") (pin "1") (pinfunction "1_1") (pintype "passive"))
      (node (ref "U5") (pin "1") (pintype "passive"))
    )
    (net (code "109") (name "/tu_6") (class "Default")
      (node (ref "R16") (pin "1") (pinfunction "1_1") (pintype "passive"))
      (node (ref "U6") (pin "1") (pintype "passive"))
    )
    (net (code "110") (name "/tu_7") (class "Default")
      (node (ref "R19") (pin "1") (pinfunction "1_1") (pintype "passive"))
      (node (ref "U7") (pin "1") (pintype "passive"))
    )
    (net (code "111") (name "/tu_8") (class "Default")
      (node (ref "R22") (pin "1") (pinfunction "1_1") (pintype "passive"))
      (node (ref "U8") (pin "1") (pintype "passive"))
    )
    (net (code "112") (name "/tu_9") (class "Default")
      (node (ref "R25") (pin "1") (pinfunction "1_1") (pintype "passive"))
      (node (ref "U9") (pin "1") (pintype "passive"))
    )
    (net (code "113") (name "/tu_10") (class "Default")
      (node (ref "R28") (pin "1") (pinfunction "1_1") (pintype "passive"))
      (node (ref "U10") (pin "1") (pintype "passive"))
    )
    (net (code "114") (name "/tu_11") (class "Default")
      (node (ref "R31") (pin "1") (pinfunction "1_1") (pintype "passive"))
      (node (ref "U11") (pin "1") (pintype "passive"))
    )
    (net (code "115") (name "/tu_12") (class "Default")
      (node (ref "R34") (pin "1") (pinfunction "1_1") (pintype "passive"))
      (node (ref "U12") (pin "1") (pintype "passive"))
    )
    (net (code "116") (name "/tu_13") (class "Default")
      (node (ref "R37") (pin "1") (pinfunction "1_1") (pintype "passive"))
      (node (ref "U13") (pin "1") (pintype "passive"))
    )
    (net (code "117") (name "/tu_14") (class "Default")
      (node (ref "R40") (pin "1") (pinfunction "1_1") (pintype "passive"))
      (node (ref "U14") (pin "1") (pintype "passive"))
    )
    (net (code "118") (name "/tu_15") (class "Default")
      (node (ref "R43") (pin "1") (pinfunction "1_1") (pintype "passive"))
      (node (ref "U15") (pin "1") (pintype "passive"))
    )
    (net (code "119") (name "/tu_16") (class "Default")
      (node (ref "R46") (pin "1") (pinfunction "1_1") (pintype "passive"))
      (node (ref "U16") (pin "1") (pintype "passive"))
    )
    (net (code "120") (name "/tu_17") (class "Default")
      (node (ref "R49") (pin "1") (pinfunction "1_1") (pintype "passive"))
      (node (ref "U18") (pin "1") (pintype "passive"))
    )
    (net (code "121") (name "/tu_18") (class "Default")
      (node (ref "R52") (pin "1") (pinfunction "1_1") (pintype "passive"))
      (node (ref "U19") (pin "1") (pintype "passive"))
    )
    (net (code "122") (name "/tu_19") (class "Default")
      (node (ref "R55") (pin "1") (pinfunction "1_1") (pintype "passive"))
      (node (ref "U20") (pin "1") (pintype "passive"))
    )
    (net (code "123") (name "/tu_20") (class "Default")
      (node (ref "R58") (pin "1") (pinfunction "1_1") (pintype "passive"))
      (node (ref "U21") (pin "1") (pintype "passive"))
    )
    (net (code "124") (name "/tu_21") (class "Default")
      (node (ref "R61") (pin "1") (pinfunction "1_1") (pintype "passive"))
      (node (ref "U22") (pin "1") (pintype "passive"))
    )
    (net (code "125") (name "/tu_22") (class "Default")
      (node (ref "R64") (pin "1") (pinfunction "1_1") (pintype "passive"))
      (node (ref "U23") (pin "1") (pintype "passive"))
    )
    (net (code "126") (name "/tu_23") (class "Default")
      (node (ref "R67") (pin "1") (pinfunction "1_1") (pintype "passive"))
      (node (ref "U24") (pin "1") (pintype "passive"))
    )
    (net (code "127") (name "/tu_24") (class "Default")
      (node (ref "R70") (pin "1") (pinfunction "1_1") (pintype "passive"))
      (node (ref "U25") (pin "1") (pintype "passive"))
    )
    (net (code "128") (name "GND") (class "Default")
      (node (ref "C1") (pin "1") (pinfunction "1_1") (pintype "passive"))
      (node (ref "C2") (pin "1") (pinfunction "1_1") (pintype "passive"))
      (node (ref "R145") (pin "1") (pinfunction "1_1") (pintype "passive"))
      (node (ref "R146") (pin "1") (pinfunction "1_1") (pintype "passive"))
      (node (ref "R147") (pin "1") (pinfunction "1_1") (pintype "passive"))
      (node (ref "R148") (pin "1") (pinfunction "1_1") (pintype "passive"))
      (node (ref "U17") (pin "2") (pinfunction "-V_inp_2") (pintype "passive"))
      (node (ref "U17") (pin "4") (pinfunction "-V_out_4") (pintype "passive"))
      (node (ref "U34") (pin "12") (pinfunction "VSS_12") (pintype "power_in"))
      (node (ref "U34") (pin "15") (pinfunction "E_15") (pintype "passive"))
      (node (ref "U35") (pin "13") (pinfunction "OE_13") (pintype "power_in"))
      (node (ref "U35") (pin "8") (pinfunction "GND_8") (pintype "power_in"))
      (node (ref "U36") (pin "13") (pinfunction "OE_13") (pintype "power_in"))
      (node (ref "U36") (pin "8") (pinfunction "GND_8") (pintype "power_in"))
      (node (ref "XP1") (pin "29") (pinfunction "B10_29") (pintype "passive"))
    )
    (net (code "129") (name "GND_5V") (class "Default")
      (node (ref "R1") (pin "2") (pinfunction "2_2") (pintype "passive"))
      (node (ref "R10") (pin "2") (pinfunction "2_2") (pintype "passive"))
      (node (ref "R12") (pin "2") (pinfunction "2_2") (pintype "passive"))
      (node (ref "R13") (pin "2") (pinfunction "2_2") (pintype "passive"))
      (node (ref "R15") (pin "2") (pinfunction "2_2") (pintype "passive"))
      (node (ref "R16") (pin "2") (pinfunction "2_2") (pintype "passive"))
      (node (ref "R18") (pin "2") (pinfunction "2_2") (pintype "passive"))
      (node (ref "R19") (pin "2") (pinfunction "2_2") (pintype "passive"))
      (node (ref "R21") (pin "2") (pinfunction "2_2") (pintype "passive"))
      (node (ref "R22") (pin "2") (pinfunction "2_2") (pintype "passive"))
      (node (ref "R24") (pin "2") (pinfunction "2_2") (pintype "passive"))
      (node (ref "R25") (pin "2") (pinfunction "2_2") (pintype "passive"))
      (node (ref "R27") (pin "2") (pinfunction "2_2") (pintype "passive"))
      (node (ref "R28") (pin "2") (pinfunction "2_2") (pintype "passive"))
      (node (ref "R3") (pin "2") (pinfunction "2_2") (pintype "passive"))
      (node (ref "R30") (pin "2") (pinfunction "2_2") (pintype "passive"))
      (node (ref "R31") (pin "2") (pinfunction "2_2") (pintype "passive"))
      (node (ref "R33") (pin "2") (pinfunction "2_2") (pintype "passive"))
      (node (ref "R34") (pin "2") (pinfunction "2_2") (pintype "passive"))
      (node (ref "R36") (pin "2") (pinfunction "2_2") (pintype "passive"))
      (node (ref "R37") (pin "2") (pinfunction "2_2") (pintype "passive"))
      (node (ref "R39") (pin "2") (pinfunction "2_2") (pintype "passive"))
      (node (ref "R4") (pin "2") (pinfunction "2_2") (pintype "passive"))
      (node (ref "R40") (pin "2") (pinfunction "2_2") (pintype "passive"))
      (node (ref "R42") (pin "2") (pinfunction "2_2") (pintype "passive"))
      (node (ref "R43") (pin "2") (pinfunction "2_2") (pintype "passive"))
      (node (ref "R45") (pin "2") (pinfunction "2_2") (pintype "passive"))
      (node (ref "R46") (pin "2") (pinfunction "2_2") (pintype "passive"))
      (node (ref "R48") (pin "2") (pinfunction "2_2") (pintype "passive"))
      (node (ref "R49") (pin "2") (pinfunction "2_2") (pintype "passive"))
      (node (ref "R51") (pin "2") (pinfunction "2_2") (pintype "passive"))
      (node (ref "R52") (pin "2") (pinfunction "2_2") (pintype "passive"))
      (node (ref "R54") (pin "2") (pinfunction "2_2") (pintype "passive"))
      (node (ref "R55") (pin "2") (pinfunction "2_2") (pintype "passive"))
      (node (ref "R57") (pin "2") (pinfunction "2_2") (pintype "passive"))
      (node (ref "R58") (pin "2") (pinfunction "2_2") (pintype "passive"))
      (node (ref "R6") (pin "2") (pinfunction "2_2") (pintype "passive"))
      (node (ref "R60") (pin "2") (pinfunction "2_2") (pintype "passive"))
      (node (ref "R61") (pin "2") (pinfunction "2_2") (pintype "passive"))
      (node (ref "R63") (pin "2") (pinfunction "2_2") (pintype "passive"))
      (node (ref "R64") (pin "2") (pinfunction "2_2") (pintype "passive"))
      (node (ref "R66") (pin "2") (pinfunction "2_2") (pintype "passive"))
      (node (ref "R67") (pin "2") (pinfunction "2_2") (pintype "passive"))
      (node (ref "R69") (pin "2") (pinfunction "2_2") (pintype "passive"))
      (node (ref "R7") (pin "2") (pinfunction "2_2") (pintype "passive"))
      (node (ref "R70") (pin "2") (pinfunction "2_2") (pintype "passive"))
      (node (ref "R72") (pin "2") (pinfunction "2_2") (pintype "passive"))
      (node (ref "R9") (pin "2") (pinfunction "2_2") (pintype "passive"))
    )
    (net (code "130") (name "GND_12V") (class "Default")
      (node (ref "VT1") (pin "3") (pintype "power_in"))
      (node (ref "VT10") (pin "3") (pintype "power_in"))
      (node (ref "VT11") (pin "3") (pintype "power_in"))
      (node (ref "VT12") (pin "3") (pintype "power_in"))
      (node (ref "VT13") (pin "3") (pintype "power_in"))
      (node (ref "VT14") (pin "3") (pintype "power_in"))
      (node (ref "VT15") (pin "3") (pintype "power_in"))
      (node (ref "VT16") (pin "3") (pintype "power_in"))
      (node (ref "VT17") (pin "3") (pintype "power_in"))
      (node (ref "VT18") (pin "3") (pintype "power_in"))
      (node (ref "VT19") (pin "3") (pintype "power_in"))
      (node (ref "VT2") (pin "3") (pintype "power_in"))
      (node (ref "VT20") (pin "3") (pintype "power_in"))
      (node (ref "VT21") (pin "3") (pintype "power_in"))
      (node (ref "VT22") (pin "3") (pintype "power_in"))
      (node (ref "VT23") (pin "3") (pintype "power_in"))
      (node (ref "VT24") (pin "3") (pintype "power_in"))
      (node (ref "VT3") (pin "3") (pintype "power_in"))
      (node (ref "VT4") (pin "3") (pintype "power_in"))
      (node (ref "VT5") (pin "3") (pintype "power_in"))
      (node (ref "VT6") (pin "3") (pintype "power_in"))
      (node (ref "VT7") (pin "3") (pintype "power_in"))
      (node (ref "VT8") (pin "3") (pintype "power_in"))
      (node (ref "VT9") (pin "3") (pintype "power_in"))
    )
    (net (code "131") (name "Net-(K1-A1)") (class "Default")
      (node (ref "K1") (pin "1") (pinfunction "A1_1") (pintype "passive"))
      (node (ref "VD1") (pin "2") (pintype "passive"))
      (node (ref "VT1") (pin "2") (pintype "power_in"))
    )
    (net (code "132") (name "Net-(K2-A1)") (class "Default")
      (node (ref "K2") (pin "1") (pinfunction "A1_1") (pintype "passive"))
      (node (ref "VD2") (pin "2") (pintype "passive"))
      (node (ref "VT2") (pin "2") (pintype "power_in"))
    )
    (net (code "133") (name "Net-(K3-A1)") (class "Default")
      (node (ref "K3") (pin "1") (pinfunction "A1_1") (pintype "passive"))
      (node (ref "VD3") (pin "2") (pintype "passive"))
      (node (ref "VT3") (pin "2") (pintype "power_in"))
    )
    (net (code "134") (name "Net-(K4-A1)") (class "Default")
      (node (ref "K4") (pin "1") (pinfunction "A1_1") (pintype "passive"))
      (node (ref "VD4") (pin "2") (pintype "passive"))
      (node (ref "VT4") (pin "2") (pintype "power_in"))
    )
    (net (code "135") (name "Net-(K5-A1)") (class "Default")
      (node (ref "K5") (pin "1") (pinfunction "A1_1") (pintype "passive"))
      (node (ref "VD5") (pin "2") (pintype "passive"))
      (node (ref "VT5") (pin "2") (pintype "power_in"))
    )
    (net (code "136") (name "Net-(K6-A1)") (class "Default")
      (node (ref "K6") (pin "1") (pinfunction "A1_1") (pintype "passive"))
      (node (ref "VD6") (pin "2") (pintype "passive"))
      (node (ref "VT6") (pin "2") (pintype "power_in"))
    )
    (net (code "137") (name "Net-(K7-A1)") (class "Default")
      (node (ref "K7") (pin "1") (pinfunction "A1_1") (pintype "passive"))
      (node (ref "VD7") (pin "2") (pintype "passive"))
      (node (ref "VT7") (pin "2") (pintype "power_in"))
    )
    (net (code "138") (name "Net-(K8-A1)") (class "Default")
      (node (ref "K8") (pin "1") (pinfunction "A1_1") (pintype "passive"))
      (node (ref "VD8") (pin "2") (pintype "passive"))
      (node (ref "VT8") (pin "2") (pintype "power_in"))
    )
    (net (code "139") (name "Net-(K9-A1)") (class "Default")
      (node (ref "K9") (pin "1") (pinfunction "A1_1") (pintype "passive"))
      (node (ref "VD9") (pin "2") (pintype "passive"))
      (node (ref "VT9") (pin "2") (pintype "power_in"))
    )
    (net (code "140") (name "Net-(K10-A1)") (class "Default")
      (node (ref "K10") (pin "1") (pinfunction "A1_1") (pintype "passive"))
      (node (ref "VD10") (pin "2") (pintype "passive"))
      (node (ref "VT10") (pin "2") (pintype "power_in"))
    )
    (net (code "141") (name "Net-(K11-A1)") (class "Default")
      (node (ref "K11") (pin "1") (pinfunction "A1_1") (pintype "passive"))
      (node (ref "VD11") (pin "2") (pintype "passive"))
      (node (ref "VT11") (pin "2") (pintype "power_in"))
    )
    (net (code "142") (name "Net-(K12-A1)") (class "Default")
      (node (ref "K12") (pin "1") (pinfunction "A1_1") (pintype "passive"))
      (node (ref "VD12") (pin "2") (pintype "passive"))
      (node (ref "VT12") (pin "2") (pintype "power_in"))
    )
    (net (code "143") (name "Net-(K13-A1)") (class "Default")
      (node (ref "K13") (pin "1") (pinfunction "A1_1") (pintype "passive"))
      (node (ref "VD13") (pin "2") (pintype "passive"))
      (node (ref "VT13") (pin "2") (pintype "power_in"))
    )
    (net (code "144") (name "Net-(K14-A1)") (class "Default")
      (node (ref "K14") (pin "1") (pinfunction "A1_1") (pintype "passive"))
      (node (ref "VD14") (pin "2") (pintype "passive"))
      (node (ref "VT14") (pin "2") (pintype "power_in"))
    )
    (net (code "145") (name "Net-(K15-A1)") (class "Default")
      (node (ref "K15") (pin "1") (pinfunction "A1_1") (pintype "passive"))
      (node (ref "VD15") (pin "2") (pintype "passive"))
      (node (ref "VT15") (pin "2") (pintype "power_in"))
    )
    (net (code "146") (name "Net-(K16-A1)") (class "Default")
      (node (ref "K16") (pin "1") (pinfunction "A1_1") (pintype "passive"))
      (node (ref "VD16") (pin "2") (pintype "passive"))
      (node (ref "VT16") (pin "2") (pintype "power_in"))
    )
    (net (code "147") (name "Net-(K17-A1)") (class "Default")
      (node (ref "K17") (pin "1") (pinfunction "A1_1") (pintype "passive"))
      (node (ref "VD17") (pin "2") (pintype "passive"))
      (node (ref "VT17") (pin "2") (pintype "power_in"))
    )
    (net (code "148") (name "Net-(K18-A1)") (class "Default")
      (node (ref "K18") (pin "1") (pinfunction "A1_1") (pintype "passive"))
      (node (ref "VD18") (pin "2") (pintype "passive"))
      (node (ref "VT18") (pin "2") (pintype "power_in"))
    )
    (net (code "149") (name "Net-(K19-A1)") (class "Default")
      (node (ref "K19") (pin "1") (pinfunction "A1_1") (pintype "passive"))
      (node (ref "VD19") (pin "2") (pintype "passive"))
      (node (ref "VT19") (pin "2") (pintype "power_in"))
    )
    (net (code "150") (name "Net-(K20-A1)") (class "Default")
      (node (ref "K20") (pin "1") (pinfunction "A1_1") (pintype "passive"))
      (node (ref "VD20") (pin "2") (pintype "passive"))
      (node (ref "VT20") (pin "2") (pintype "power_in"))
    )
    (net (code "151") (name "Net-(K21-A1)") (class "Default")
      (node (ref "K21") (pin "1") (pinfunction "A1_1") (pintype "passive"))
      (node (ref "VD21") (pin "2") (pintype "passive"))
      (node (ref "VT21") (pin "2") (pintype "power_in"))
    )
    (net (code "152") (name "Net-(K22-A1)") (class "Default")
      (node (ref "K22") (pin "1") (pinfunction "A1_1") (pintype "passive"))
      (node (ref "VD22") (pin "2") (pintype "passive"))
      (node (ref "VT22") (pin "2") (pintype "power_in"))
    )
    (net (code "153") (name "Net-(K23-A1)") (class "Default")
      (node (ref "K23") (pin "1") (pinfunction "A1_1") (pintype "passive"))
      (node (ref "VD23") (pin "2") (pintype "passive"))
      (node (ref "VT23") (pin "2") (pintype "power_in"))
    )
    (net (code "154") (name "Net-(K24-A1)") (class "Default")
      (node (ref "K24") (pin "1") (pinfunction "A1_1") (pintype "passive"))
      (node (ref "VD24") (pin "2") (pintype "passive"))
      (node (ref "VT24") (pin "2") (pintype "power_in"))
    )
    (net (code "155") (name "Net-(R2-Pad1)") (class "Default")
      (node (ref "R2") (pin "1") (pinfunction "1_1") (pintype "passive"))
      (node (ref "U1") (pin "3") (pintype "passive"))
    )
    (net (code "156") (name "Net-(R2-Pad2)") (class "Default")
      (node (ref "R2") (pin "2") (pinfunction "2_2") (pintype "passive"))
      (node (ref "VT1") (pin "1") (pintype "power_in"))
    )
    (net (code "157") (name "Net-(R3-Pad1)") (class "Default")
      (node (ref "R3") (pin "1") (pinfunction "1_1") (pintype "passive"))
      (node (ref "U1") (pin "2") (pintype "passive"))
    )
    (net (code "158") (name "Net-(R5-Pad1)") (class "Default")
      (node (ref "R5") (pin "1") (pinfunction "1_1") (pintype "passive"))
      (node (ref "U2") (pin "3") (pintype "passive"))
    )
    (net (code "159") (name "Net-(R5-Pad2)") (class "Default")
      (node (ref "R5") (pin "2") (pinfunction "2_2") (pintype "passive"))
      (node (ref "VT2") (pin "1") (pintype "power_in"))
    )
    (net (code "160") (name "Net-(R6-Pad1)") (class "Default")
      (node (ref "R6") (pin "1") (pinfunction "1_1") (pintype "passive"))
      (node (ref "U2") (pin "2") (pintype "passive"))
    )
    (net (code "161") (name "Net-(R8-Pad1)") (class "Default")
      (node (ref "R8") (pin "1") (pinfunction "1_1") (pintype "passive"))
      (node (ref "U3") (pin "3") (pintype "passive"))
    )
    (net (code "162") (name "Net-(R8-Pad2)") (class "Default")
      (node (ref "R8") (pin "2") (pinfunction "2_2") (pintype "passive"))
      (node (ref "VT3") (pin "1") (pintype "power_in"))
    )
    (net (code "163") (name "Net-(R9-Pad1)") (class "Default")
      (node (ref "R9") (pin "1") (pinfunction "1_1") (pintype "passive"))
      (node (ref "U3") (pin "2") (pintype "passive"))
    )
    (net (code "164") (name "Net-(R11-Pad1)") (class "Default")
      (node (ref "R11") (pin "1") (pinfunction "1_1") (pintype "passive"))
      (node (ref "U4") (pin "3") (pintype "passive"))
    )
    (net (code "165") (name "Net-(R11-Pad2)") (class "Default")
      (node (ref "R11") (pin "2") (pinfunction "2_2") (pintype "passive"))
      (node (ref "VT4") (pin "1") (pintype "power_in"))
    )
    (net (code "166") (name "Net-(R12-Pad1)") (class "Default")
      (node (ref "R12") (pin "1") (pinfunction "1_1") (pintype "passive"))
      (node (ref "U4") (pin "2") (pintype "passive"))
    )
    (net (code "167") (name "Net-(R14-Pad1)") (class "Default")
      (node (ref "R14") (pin "1") (pinfunction "1_1") (pintype "passive"))
      (node (ref "U5") (pin "3") (pintype "passive"))
    )
    (net (code "168") (name "Net-(R14-Pad2)") (class "Default")
      (node (ref "R14") (pin "2") (pinfunction "2_2") (pintype "passive"))
      (node (ref "VT5") (pin "1") (pintype "power_in"))
    )
    (net (code "169") (name "Net-(R15-Pad1)") (class "Default")
      (node (ref "R15") (pin "1") (pinfunction "1_1") (pintype "passive"))
      (node (ref "U5") (pin "2") (pintype "passive"))
    )
    (net (code "170") (name "Net-(R17-Pad1)") (class "Default")
      (node (ref "R17") (pin "1") (pinfunction "1_1") (pintype "passive"))
      (node (ref "U6") (pin "3") (pintype "passive"))
    )
    (net (code "171") (name "Net-(R17-Pad2)") (class "Default")
      (node (ref "R17") (pin "2") (pinfunction "2_2") (pintype "passive"))
      (node (ref "VT6") (pin "1") (pintype "power_in"))
    )
    (net (code "172") (name "Net-(R18-Pad1)") (class "Default")
      (node (ref "R18") (pin "1") (pinfunction "1_1") (pintype "passive"))
      (node (ref "U6") (pin "2") (pintype "passive"))
    )
    (net (code "173") (name "Net-(R20-Pad1)") (class "Default")
      (node (ref "R20") (pin "1") (pinfunction "1_1") (pintype "passive"))
      (node (ref "U7") (pin "3") (pintype "passive"))
    )
    (net (code "174") (name "Net-(R20-Pad2)") (class "Default")
      (node (ref "R20") (pin "2") (pinfunction "2_2") (pintype "passive"))
      (node (ref "VT7") (pin "1") (pintype "power_in"))
    )
    (net (code "175") (name "Net-(R21-Pad1)") (class "Default")
      (node (ref "R21") (pin "1") (pinfunction "1_1") (pintype "passive"))
      (node (ref "U7") (pin "2") (pintype "passive"))
    )
    (net (code "176") (name "Net-(R23-Pad1)") (class "Default")
      (node (ref "R23") (pin "1") (pinfunction "1_1") (pintype "passive"))
      (node (ref "U8") (pin "3") (pintype "passive"))
    )
    (net (code "177") (name "Net-(R23-Pad2)") (class "Default")
      (node (ref "R23") (pin "2") (pinfunction "2_2") (pintype "passive"))
      (node (ref "VT8") (pin "1") (pintype "power_in"))
    )
    (net (code "178") (name "Net-(R24-Pad1)") (class "Default")
      (node (ref "R24") (pin "1") (pinfunction "1_1") (pintype "passive"))
      (node (ref "U8") (pin "2") (pintype "passive"))
    )
    (net (code "179") (name "Net-(R26-Pad1)") (class "Default")
      (node (ref "R26") (pin "1") (pinfunction "1_1") (pintype "passive"))
      (node (ref "U9") (pin "3") (pintype "passive"))
    )
    (net (code "180") (name "Net-(R26-Pad2)") (class "Default")
      (node (ref "R26") (pin "2") (pinfunction "2_2") (pintype "passive"))
      (node (ref "VT9") (pin "1") (pintype "power_in"))
    )
    (net (code "181") (name "Net-(R27-Pad1)") (class "Default")
      (node (ref "R27") (pin "1") (pinfunction "1_1") (pintype "passive"))
      (node (ref "U9") (pin "2") (pintype "passive"))
    )
    (net (code "182") (name "Net-(R29-Pad1)") (class "Default")
      (node (ref "R29") (pin "1") (pinfunction "1_1") (pintype "passive"))
      (node (ref "U10") (pin "3") (pintype "passive"))
    )
    (net (code "183") (name "Net-(R29-Pad2)") (class "Default")
      (node (ref "R29") (pin "2") (pinfunction "2_2") (pintype "passive"))
      (node (ref "VT10") (pin "1") (pintype "power_in"))
    )
    (net (code "184") (name "Net-(R30-Pad1)") (class "Default")
      (node (ref "R30") (pin "1") (pinfunction "1_1") (pintype "passive"))
      (node (ref "U10") (pin "2") (pintype "passive"))
    )
    (net (code "185") (name "Net-(R32-Pad1)") (class "Default")
      (node (ref "R32") (pin "1") (pinfunction "1_1") (pintype "passive"))
      (node (ref "U11") (pin "3") (pintype "passive"))
    )
    (net (code "186") (name "Net-(R32-Pad2)") (class "Default")
      (node (ref "R32") (pin "2") (pinfunction "2_2") (pintype "passive"))
      (node (ref "VT11") (pin "1") (pintype "power_in"))
    )
    (net (code "187") (name "Net-(R33-Pad1)") (class "Default")
      (node (ref "R33") (pin "1") (pinfunction "1_1") (pintype "passive"))
      (node (ref "U11") (pin "2") (pintype "passive"))
    )
    (net (code "188") (name "Net-(R35-Pad1)") (class "Default")
      (node (ref "R35") (pin "1") (pinfunction "1_1") (pintype "passive"))
      (node (ref "U12") (pin "3") (pintype "passive"))
    )
    (net (code "189") (name "Net-(R35-Pad2)") (class "Default")
      (node (ref "R35") (pin "2") (pinfunction "2_2") (pintype "passive"))
      (node (ref "VT12") (pin "1") (pintype "power_in"))
    )
    (net (code "190") (name "Net-(R36-Pad1)") (class "Default")
      (node (ref "R36") (pin "1") (pinfunction "1_1") (pintype "passive"))
      (node (ref "U12") (pin "2") (pintype "passive"))
    )
    (net (code "191") (name "Net-(R38-Pad1)") (class "Default")
      (node (ref "R38") (pin "1") (pinfunction "1_1") (pintype "passive"))
      (node (ref "U13") (pin "3") (pintype "passive"))
    )
    (net (code "192") (name "Net-(R38-Pad2)") (class "Default")
      (node (ref "R38") (pin "2") (pinfunction "2_2") (pintype "passive"))
      (node (ref "VT13") (pin "1") (pintype "power_in"))
    )
    (net (code "193") (name "Net-(R39-Pad1)") (class "Default")
      (node (ref "R39") (pin "1") (pinfunction "1_1") (pintype "passive"))
      (node (ref "U13") (pin "2") (pintype "passive"))
    )
    (net (code "194") (name "Net-(R41-Pad1)") (class "Default")
      (node (ref "R41") (pin "1") (pinfunction "1_1") (pintype "passive"))
      (node (ref "U14") (pin "3") (pintype "passive"))
    )
    (net (code "195") (name "Net-(R41-Pad2)") (class "Default")
      (node (ref "R41") (pin "2") (pinfunction "2_2") (pintype "passive"))
      (node (ref "VT14") (pin "1") (pintype "power_in"))
    )
    (net (code "196") (name "Net-(R42-Pad1)") (class "Default")
      (node (ref "R42") (pin "1") (pinfunction "1_1") (pintype "passive"))
      (node (ref "U14") (pin "2") (pintype "passive"))
    )
    (net (code "197") (name "Net-(R44-Pad1)") (class "Default")
      (node (ref "R44") (pin "1") (pinfunction "1_1") (pintype "passive"))
      (node (ref "U15") (pin "3") (pintype "passive"))
    )
    (net (code "198") (name "Net-(R44-Pad2)") (class "Default")
      (node (ref "R44") (pin "2") (pinfunction "2_2") (pintype "passive"))
      (node (ref "VT15") (pin "1") (pintype "power_in"))
    )
    (net (code "199") (name "Net-(R45-Pad1)") (class "Default")
      (node (ref "R45") (pin "1") (pinfunction "1_1") (pintype "passive"))
      (node (ref "U15") (pin "2") (pintype "passive"))
    )
    (net (code "200") (name "Net-(R47-Pad1)") (class "Default")
      (node (ref "R47") (pin "1") (pinfunction "1_1") (pintype "passive"))
      (node (ref "U16") (pin "3") (pintype "passive"))
    )
    (net (code "201") (name "Net-(R47-Pad2)") (class "Default")
      (node (ref "R47") (pin "2") (pinfunction "2_2") (pintype "passive"))
      (node (ref "VT16") (pin "1") (pintype "power_in"))
    )
    (net (code "202") (name "Net-(R48-Pad1)") (class "Default")
      (node (ref "R48") (pin "1") (pinfunction "1_1") (pintype "passive"))
      (node (ref "U16") (pin "2") (pintype "passive"))
    )
    (net (code "203") (name "Net-(R50-Pad1)") (class "Default")
      (node (ref "R50") (pin "1") (pinfunction "1_1") (pintype "passive"))
      (node (ref "U18") (pin "3") (pintype "passive"))
    )
    (net (code "204") (name "Net-(R50-Pad2)") (class "Default")
      (node (ref "R50") (pin "2") (pinfunction "2_2") (pintype "passive"))
      (node (ref "VT17") (pin "1") (pintype "power_in"))
    )
    (net (code "205") (name "Net-(R51-Pad1)") (class "Default")
      (node (ref "R51") (pin "1") (pinfunction "1_1") (pintype "passive"))
      (node (ref "U18") (pin "2") (pintype "passive"))
    )
    (net (code "206") (name "Net-(R53-Pad1)") (class "Default")
      (node (ref "R53") (pin "1") (pinfunction "1_1") (pintype "passive"))
      (node (ref "U19") (pin "3") (pintype "passive"))
    )
    (net (code "207") (name "Net-(R53-Pad2)") (class "Default")
      (node (ref "R53") (pin "2") (pinfunction "2_2") (pintype "passive"))
      (node (ref "VT18") (pin "1") (pintype "power_in"))
    )
    (net (code "208") (name "Net-(R54-Pad1)") (class "Default")
      (node (ref "R54") (pin "1") (pinfunction "1_1") (pintype "passive"))
      (node (ref "U19") (pin "2") (pintype "passive"))
    )
    (net (code "209") (name "Net-(R56-Pad1)") (class "Default")
      (node (ref "R56") (pin "1") (pinfunction "1_1") (pintype "passive"))
      (node (ref "U20") (pin "3") (pintype "passive"))
    )
    (net (code "210") (name "Net-(R56-Pad2)") (class "Default")
      (node (ref "R56") (pin "2") (pinfunction "2_2") (pintype "passive"))
      (node (ref "VT19") (pin "1") (pintype "power_in"))
    )
    (net (code "211") (name "Net-(R57-Pad1)") (class "Default")
      (node (ref "R57") (pin "1") (pinfunction "1_1") (pintype "passive"))
      (node (ref "U20") (pin "2") (pintype "passive"))
    )
    (net (code "212") (name "Net-(R59-Pad1)") (class "Default")
      (node (ref "R59") (pin "1") (pinfunction "1_1") (pintype "passive"))
      (node (ref "U21") (pin "3") (pintype "passive"))
    )
    (net (code "213") (name "Net-(R59-Pad2)") (class "Default")
      (node (ref "R59") (pin "2") (pinfunction "2_2") (pintype "passive"))
      (node (ref "VT20") (pin "1") (pintype "power_in"))
    )
    (net (code "214") (name "Net-(R60-Pad1)") (class "Default")
      (node (ref "R60") (pin "1") (pinfunction "1_1") (pintype "passive"))
      (node (ref "U21") (pin "2") (pintype "passive"))
    )
    (net (code "215") (name "Net-(R62-Pad1)") (class "Default")
      (node (ref "R62") (pin "1") (pinfunction "1_1") (pintype "passive"))
      (node (ref "U22") (pin "3") (pintype "passive"))
    )
    (net (code "216") (name "Net-(R62-Pad2)") (class "Default")
      (node (ref "R62") (pin "2") (pinfunction "2_2") (pintype "passive"))
      (node (ref "VT21") (pin "1") (pintype "power_in"))
    )
    (net (code "217") (name "Net-(R63-Pad1)") (class "Default")
      (node (ref "R63") (pin "1") (pinfunction "1_1") (pintype "passive"))
      (node (ref "U22") (pin "2") (pintype "passive"))
    )
    (net (code "218") (name "Net-(R65-Pad1)") (class "Default")
      (node (ref "R65") (pin "1") (pinfunction "1_1") (pintype "passive"))
      (node (ref "U23") (pin "3") (pintype "passive"))
    )
    (net (code "219") (name "Net-(R65-Pad2)") (class "Default")
      (node (ref "R65") (pin "2") (pinfunction "2_2") (pintype "passive"))
      (node (ref "VT22") (pin "1") (pintype "power_in"))
    )
    (net (code "220") (name "Net-(R66-Pad1)") (class "Default")
      (node (ref "R66") (pin "1") (pinfunction "1_1") (pintype "passive"))
      (node (ref "U23") (pin "2") (pintype "passive"))
    )
    (net (code "221") (name "Net-(R68-Pad1)") (class "Default")
      (node (ref "R68") (pin "1") (pinfunction "1_1") (pintype "passive"))
      (node (ref "U24") (pin "3") (pintype "passive"))
    )
    (net (code "222") (name "Net-(R68-Pad2)") (class "Default")
      (node (ref "R68") (pin "2") (pinfunction "2_2") (pintype "passive"))
      (node (ref "VT23") (pin "1") (pintype "power_in"))
    )
    (net (code "223") (name "Net-(R69-Pad1)") (class "Default")
      (node (ref "R69") (pin "1") (pinfunction "1_1") (pintype "passive"))
      (node (ref "U24") (pin "2") (pintype "passive"))
    )
    (net (code "224") (name "Net-(R71-Pad1)") (class "Default")
      (node (ref "R71") (pin "1") (pinfunction "1_1") (pintype "passive"))
      (node (ref "U25") (pin "3") (pintype "passive"))
    )
    (net (code "225") (name "Net-(R71-Pad2)") (class "Default")
      (node (ref "R71") (pin "2") (pinfunction "2_2") (pintype "passive"))
      (node (ref "VT24") (pin "1") (pintype "power_in"))
    )
    (net (code "226") (name "Net-(R72-Pad1)") (class "Default")
      (node (ref "R72") (pin "1") (pinfunction "1_1") (pintype "passive"))
      (node (ref "U25") (pin "2") (pintype "passive"))
    )
    (net (code "227") (name "unconnected-(K1-NC-Pad3)") (class "Default")
      (node (ref "K1") (pin "3") (pinfunction "NC_3") (pintype "passive"))
    )
    (net (code "228") (name "unconnected-(K2-NC-Pad3)") (class "Default")
      (node (ref "K2") (pin "3") (pinfunction "NC_3") (pintype "passive"))
    )
    (net (code "229") (name "unconnected-(K3-NC-Pad3)") (class "Default")
      (node (ref "K3") (pin "3") (pinfunction "NC_3") (pintype "passive"))
    )
    (net (code "230") (name "unconnected-(K4-NC-Pad3)") (class "Default")
      (node (ref "K4") (pin "3") (pinfunction "NC_3") (pintype "passive"))
    )
    (net (code "231") (name "unconnected-(K5-NC-Pad3)") (class "Default")
      (node (ref "K5") (pin "3") (pinfunction "NC_3") (pintype "passive"))
    )
    (net (code "232") (name "unconnected-(K6-NC-Pad3)") (class "Default")
      (node (ref "K6") (pin "3") (pinfunction "NC_3") (pintype "passive"))
    )
    (net (code "233") (name "unconnected-(K7-NC-Pad3)") (class "Default")
      (node (ref "K7") (pin "3") (pinfunction "NC_3") (pintype "passive"))
    )
    (net (code "234") (name "unconnected-(K8-NC-Pad3)") (class "Default")
      (node (ref "K8") (pin "3") (pinfunction "NC_3") (pintype "passive"))
    )
    (net (code "235") (name "unconnected-(K9-NC-Pad3)") (class "Default")
      (node (ref "K9") (pin "3") (pinfunction "NC_3") (pintype "passive"))
    )
    (net (code "236") (name "unconnected-(K10-NC-Pad3)") (class "Default")
      (node (ref "K10") (pin "3") (pinfunction "NC_3") (pintype "passive"))
    )
    (net (code "237") (name "unconnected-(K11-NC-Pad3)") (class "Default")
      (node (ref "K11") (pin "3") (pinfunction "NC_3") (pintype "passive"))
    )
    (net (code "238") (name "unconnected-(K12-NC-Pad3)") (class "Default")
      (node (ref "K12") (pin "3") (pinfunction "NC_3") (pintype "passive"))
    )
    (net (code "239") (name "unconnected-(K13-NC-Pad3)") (class "Default")
      (node (ref "K13") (pin "3") (pinfunction "NC_3") (pintype "passive"))
    )
    (net (code "240") (name "unconnected-(K14-NC-Pad3)") (class "Default")
      (node (ref "K14") (pin "3") (pinfunction "NC_3") (pintype "passive"))
    )
    (net (code "241") (name "unconnected-(K15-NC-Pad3)") (class "Default")
      (node (ref "K15") (pin "3") (pinfunction "NC_3") (pintype "passive"))
    )
    (net (code "242") (name "unconnected-(K16-NC-Pad3)") (class "Default")
      (node (ref "K16") (pin "3") (pinfunction "NC_3") (pintype "passive"))
    )
    (net (code "243") (name "unconnected-(K17-NC-Pad3)") (class "Default")
      (node (ref "K17") (pin "3") (pinfunction "NC_3") (pintype "passive"))
    )
    (net (code "244") (name "unconnected-(K18-NC-Pad3)") (class "Default")
      (node (ref "K18") (pin "3") (pinfunction "NC_3") (pintype "passive"))
    )
    (net (code "245") (name "unconnected-(K19-NC-Pad3)") (class "Default")
      (node (ref "K19") (pin "3") (pinfunction "NC_3") (pintype "passive"))
    )
    (net (code "246") (name "unconnected-(K20-NC-Pad3)") (class "Default")
      (node (ref "K20") (pin "3") (pinfunction "NC_3") (pintype "passive"))
    )
    (net (code "247") (name "unconnected-(K21-NC-Pad3)") (class "Default")
      (node (ref "K21") (pin "3") (pinfunction "NC_3") (pintype "passive"))
    )
    (net (code "248") (name "unconnected-(K22-NC-Pad3)") (class "Default")
      (node (ref "K22") (pin "3") (pinfunction "NC_3") (pintype "passive"))
    )
    (net (code "249") (name "unconnected-(K23-NC-Pad3)") (class "Default")
      (node (ref "K23") (pin "3") (pinfunction "NC_3") (pintype "passive"))
    )
    (net (code "250") (name "unconnected-(K24-NC-Pad3)") (class "Default")
      (node (ref "K24") (pin "3") (pinfunction "NC_3") (pintype "passive"))
    )
    (net (code "251") (name "unconnected-(U35-Q7S-Pad9)") (class "Default")
      (node (ref "U35") (pin "9") (pinfunction "Q7S_9") (pintype "power_in"))
    )
    (net (code "252") (name "unconnected-(U36-Q7S-Pad9)") (class "Default")
      (node (ref "U36") (pin "9") (pinfunction "Q7S_9") (pintype "power_in"))
    )
    (net (code "253") (name "unconnected-(XP1-A10-Pad10)") (class "Default")
      (node (ref "XP1") (pin "10") (pinfunction "A10_10") (pintype "passive"))
    )
    (net (code "254") (name "unconnected-(XP1-A19-Pad19)") (class "Default")
      (node (ref "XP1") (pin "19") (pinfunction "A19_19") (pintype "passive"))
    )
  )
)
